# testerusb.net
KiCad netlist of a schematic drawn in EAGLE
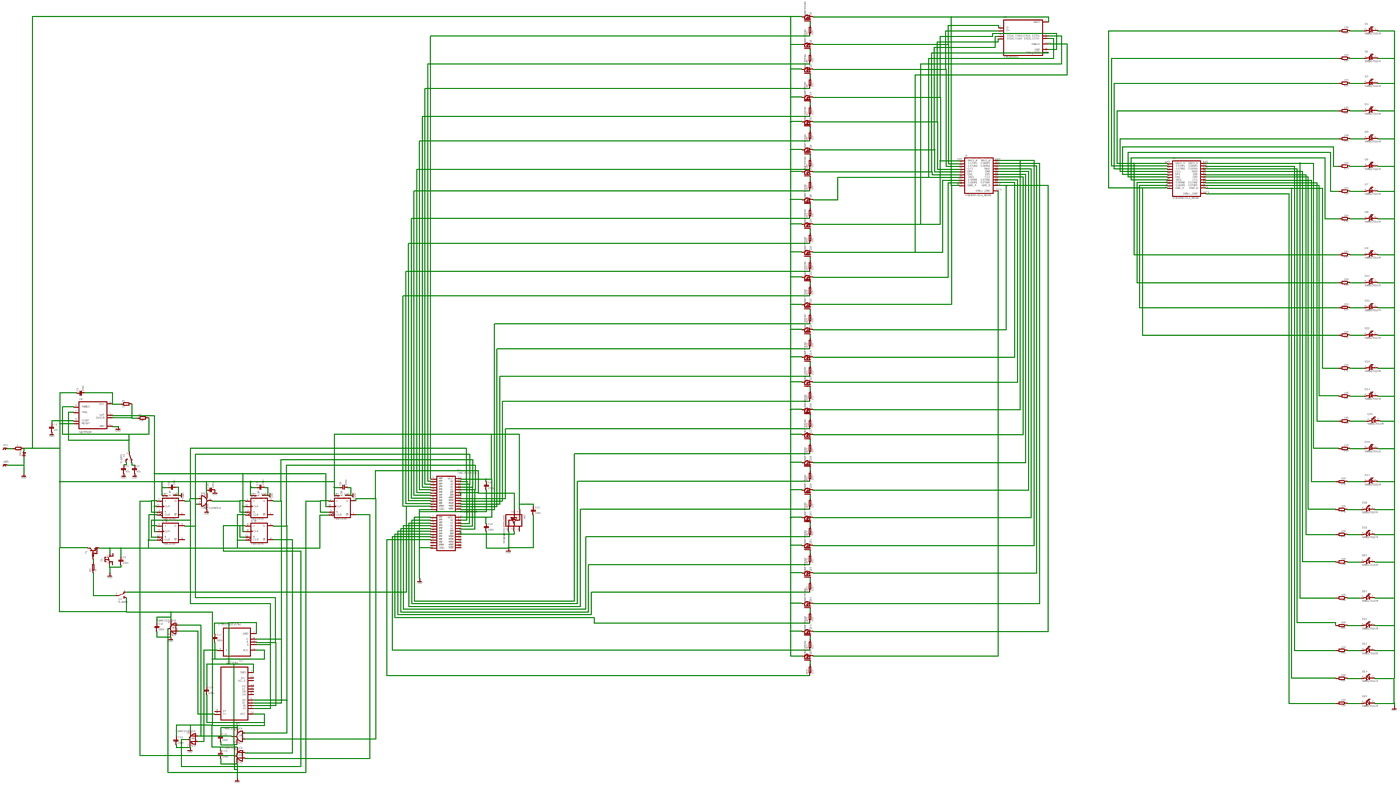
[diagram p0: schematic, sheet 1, overview]
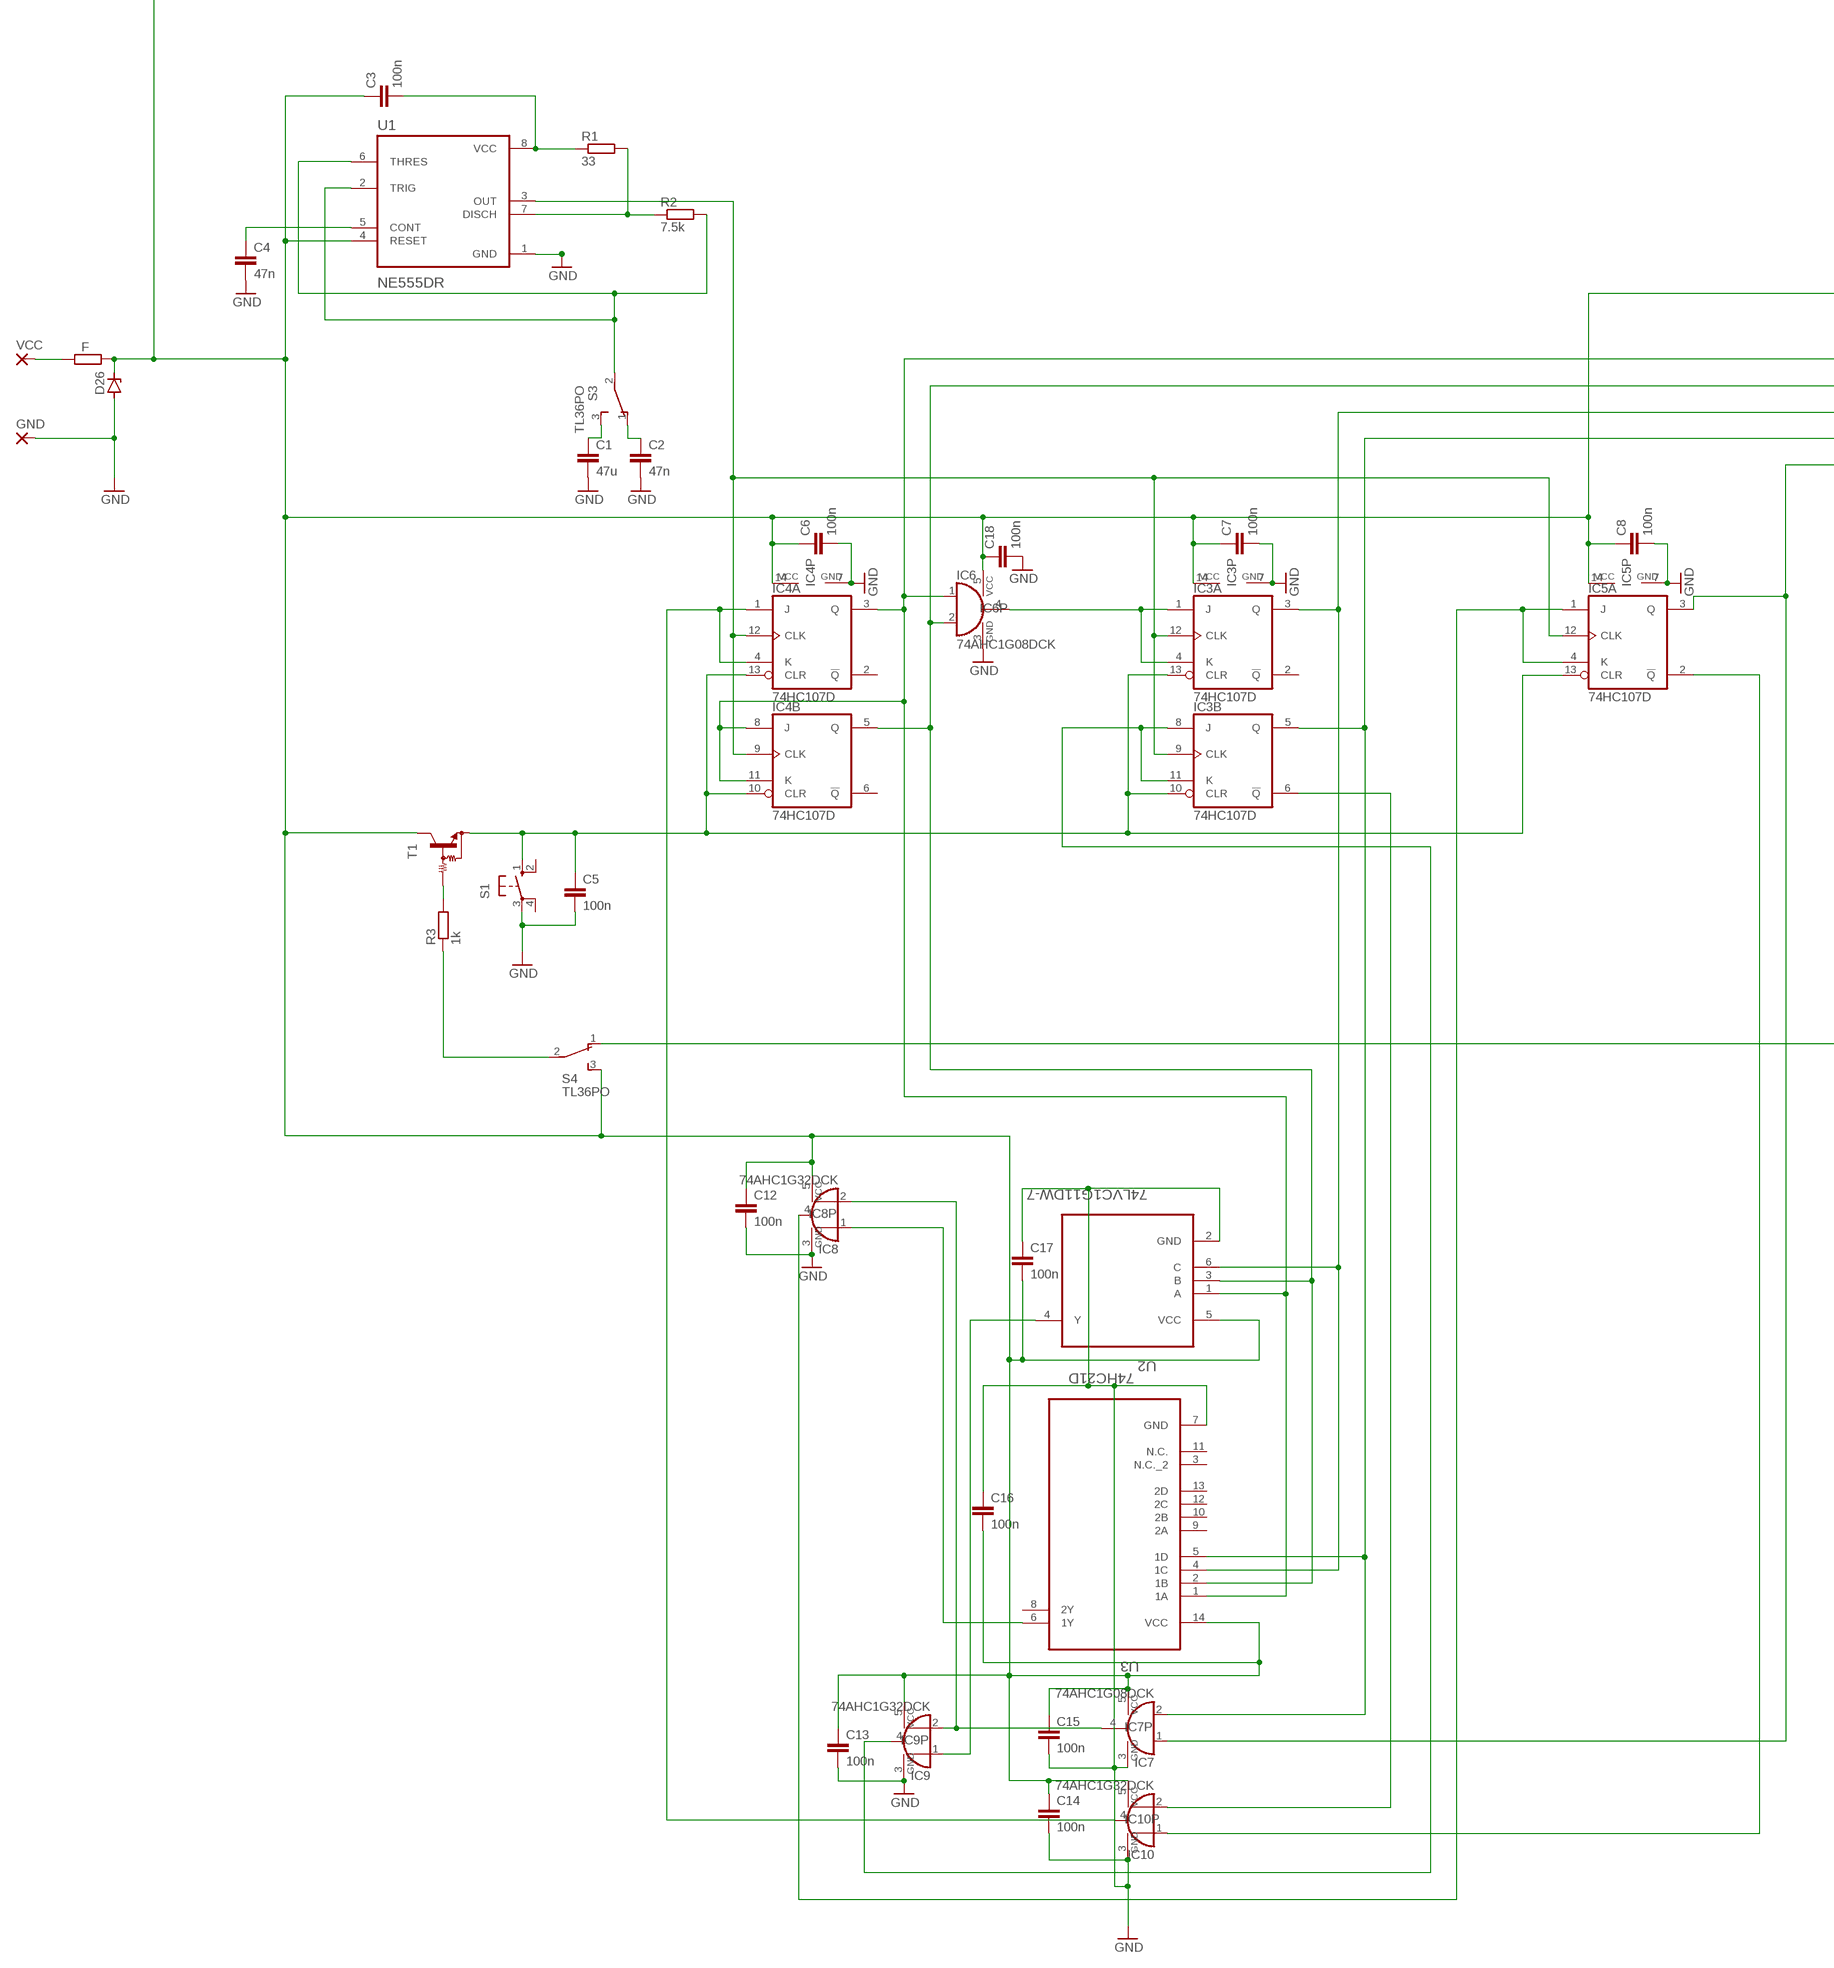
[diagram p1: schematic, sheet 1, part 1 of 6]
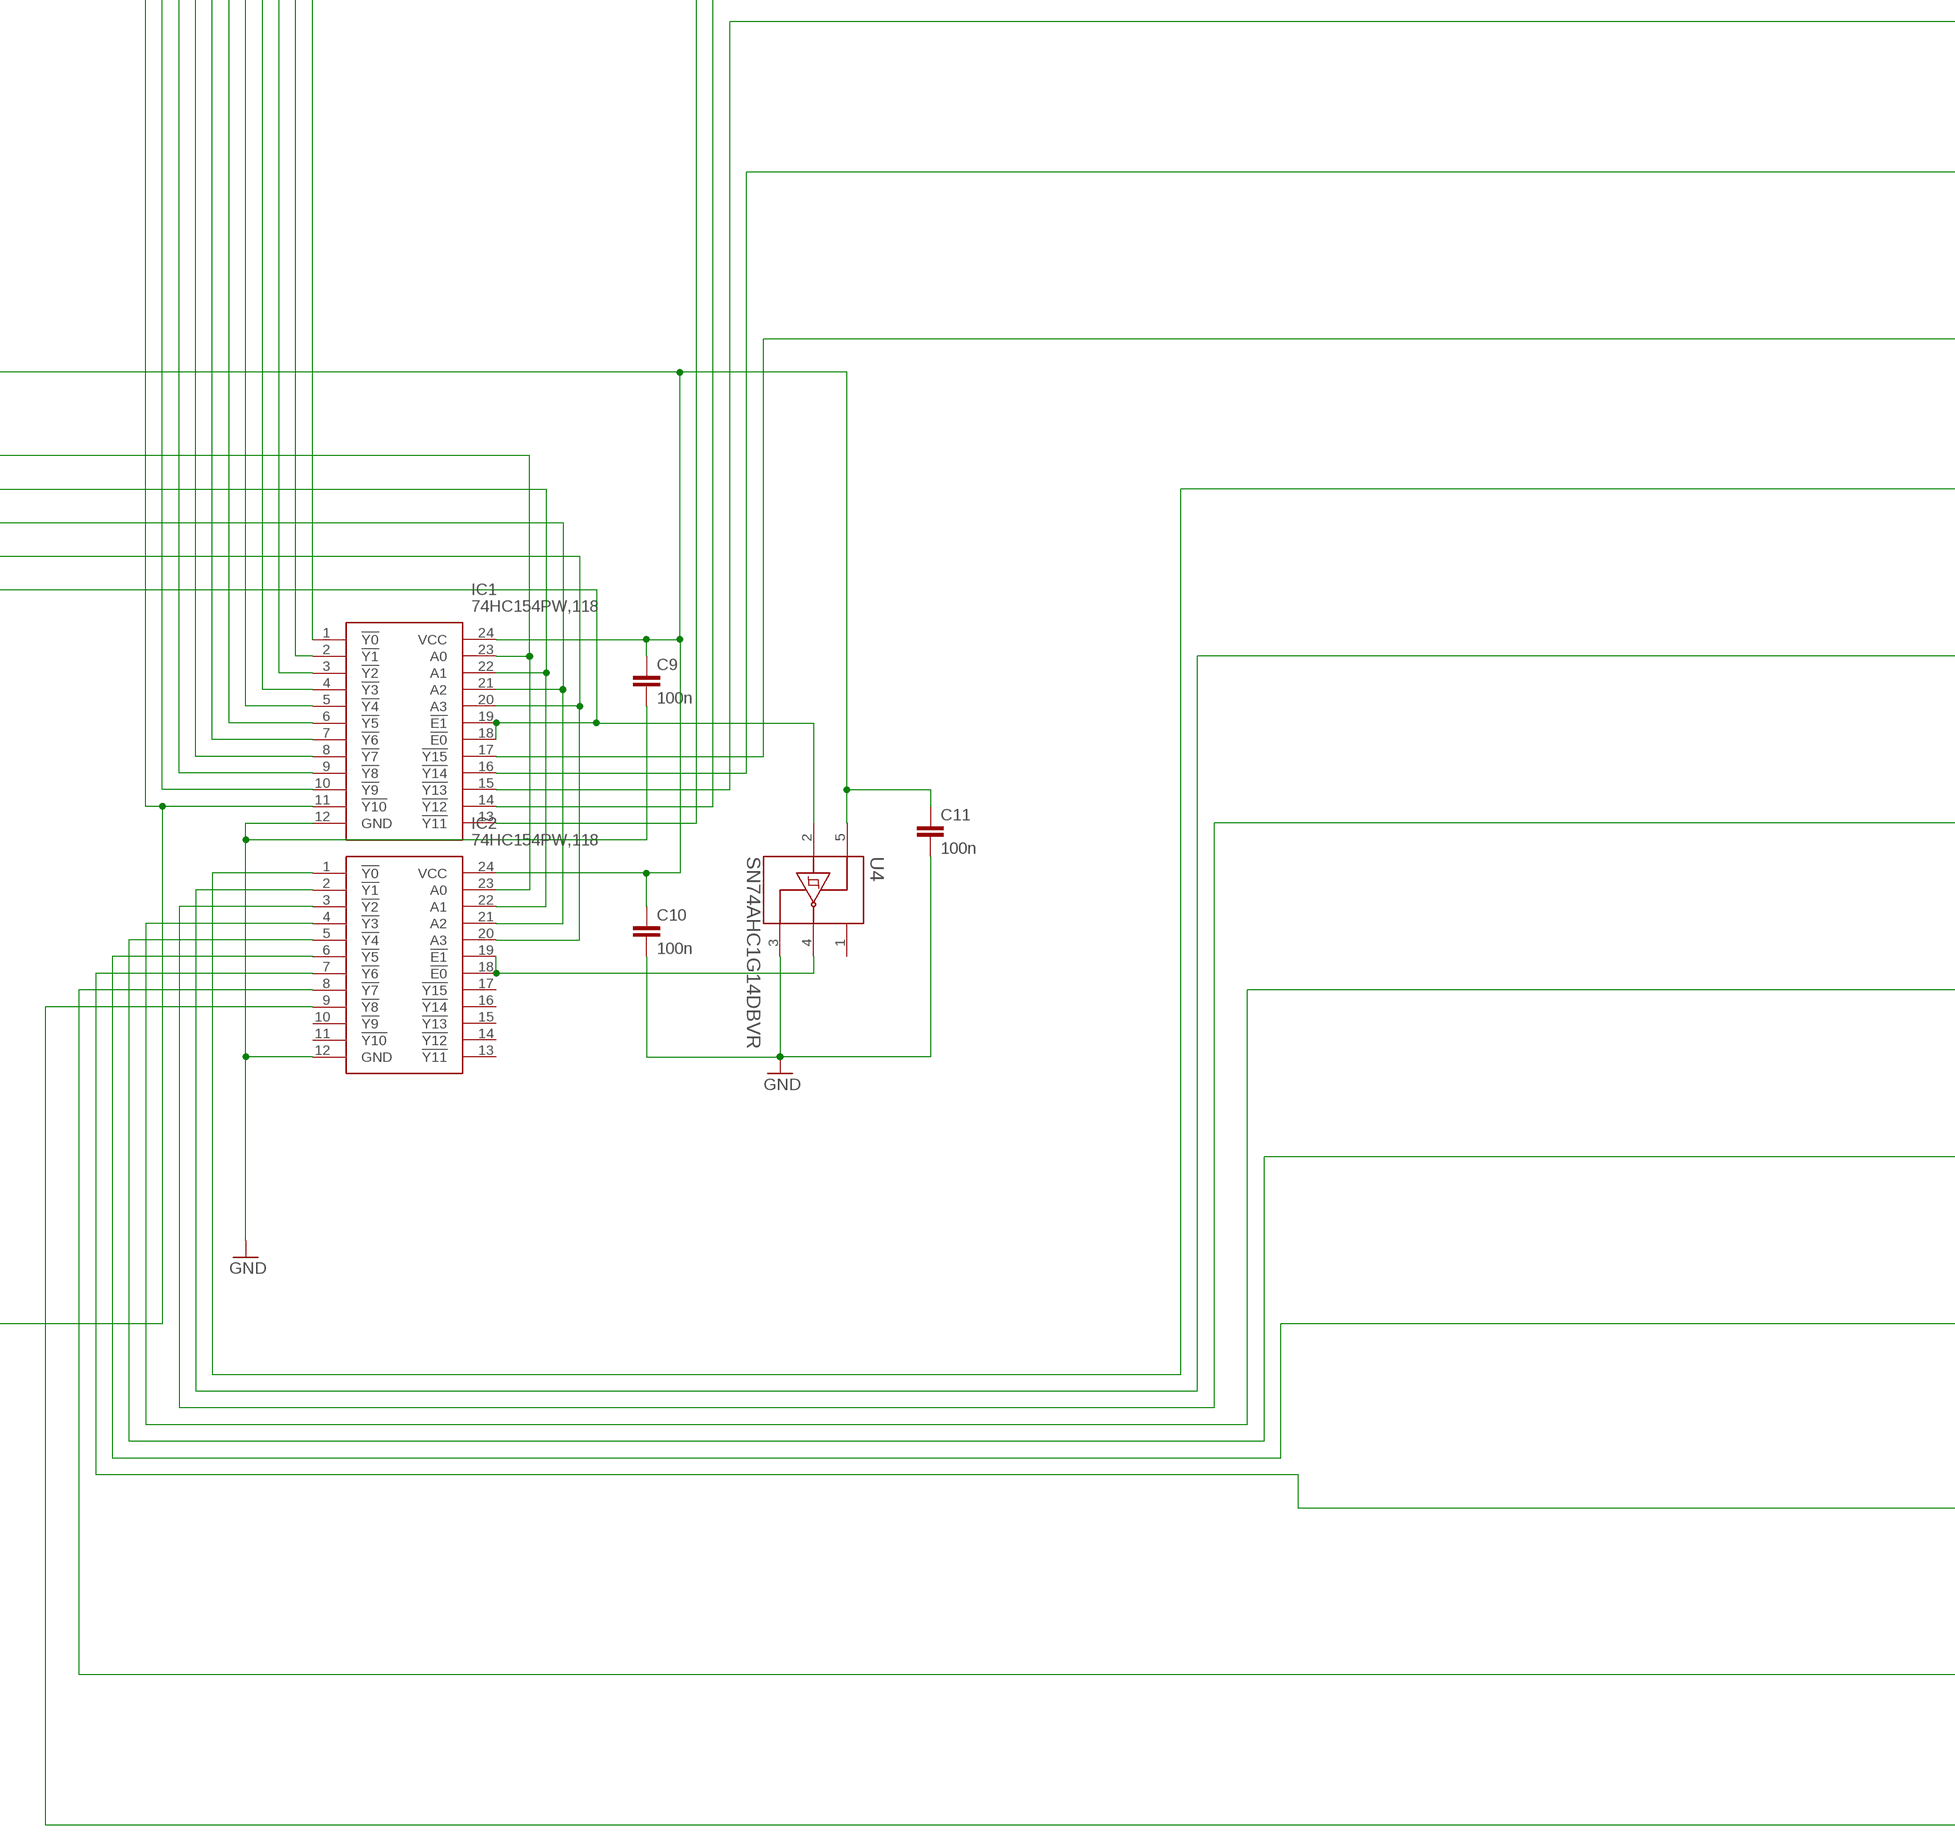
[diagram p2: schematic, sheet 1, part 2 of 6]
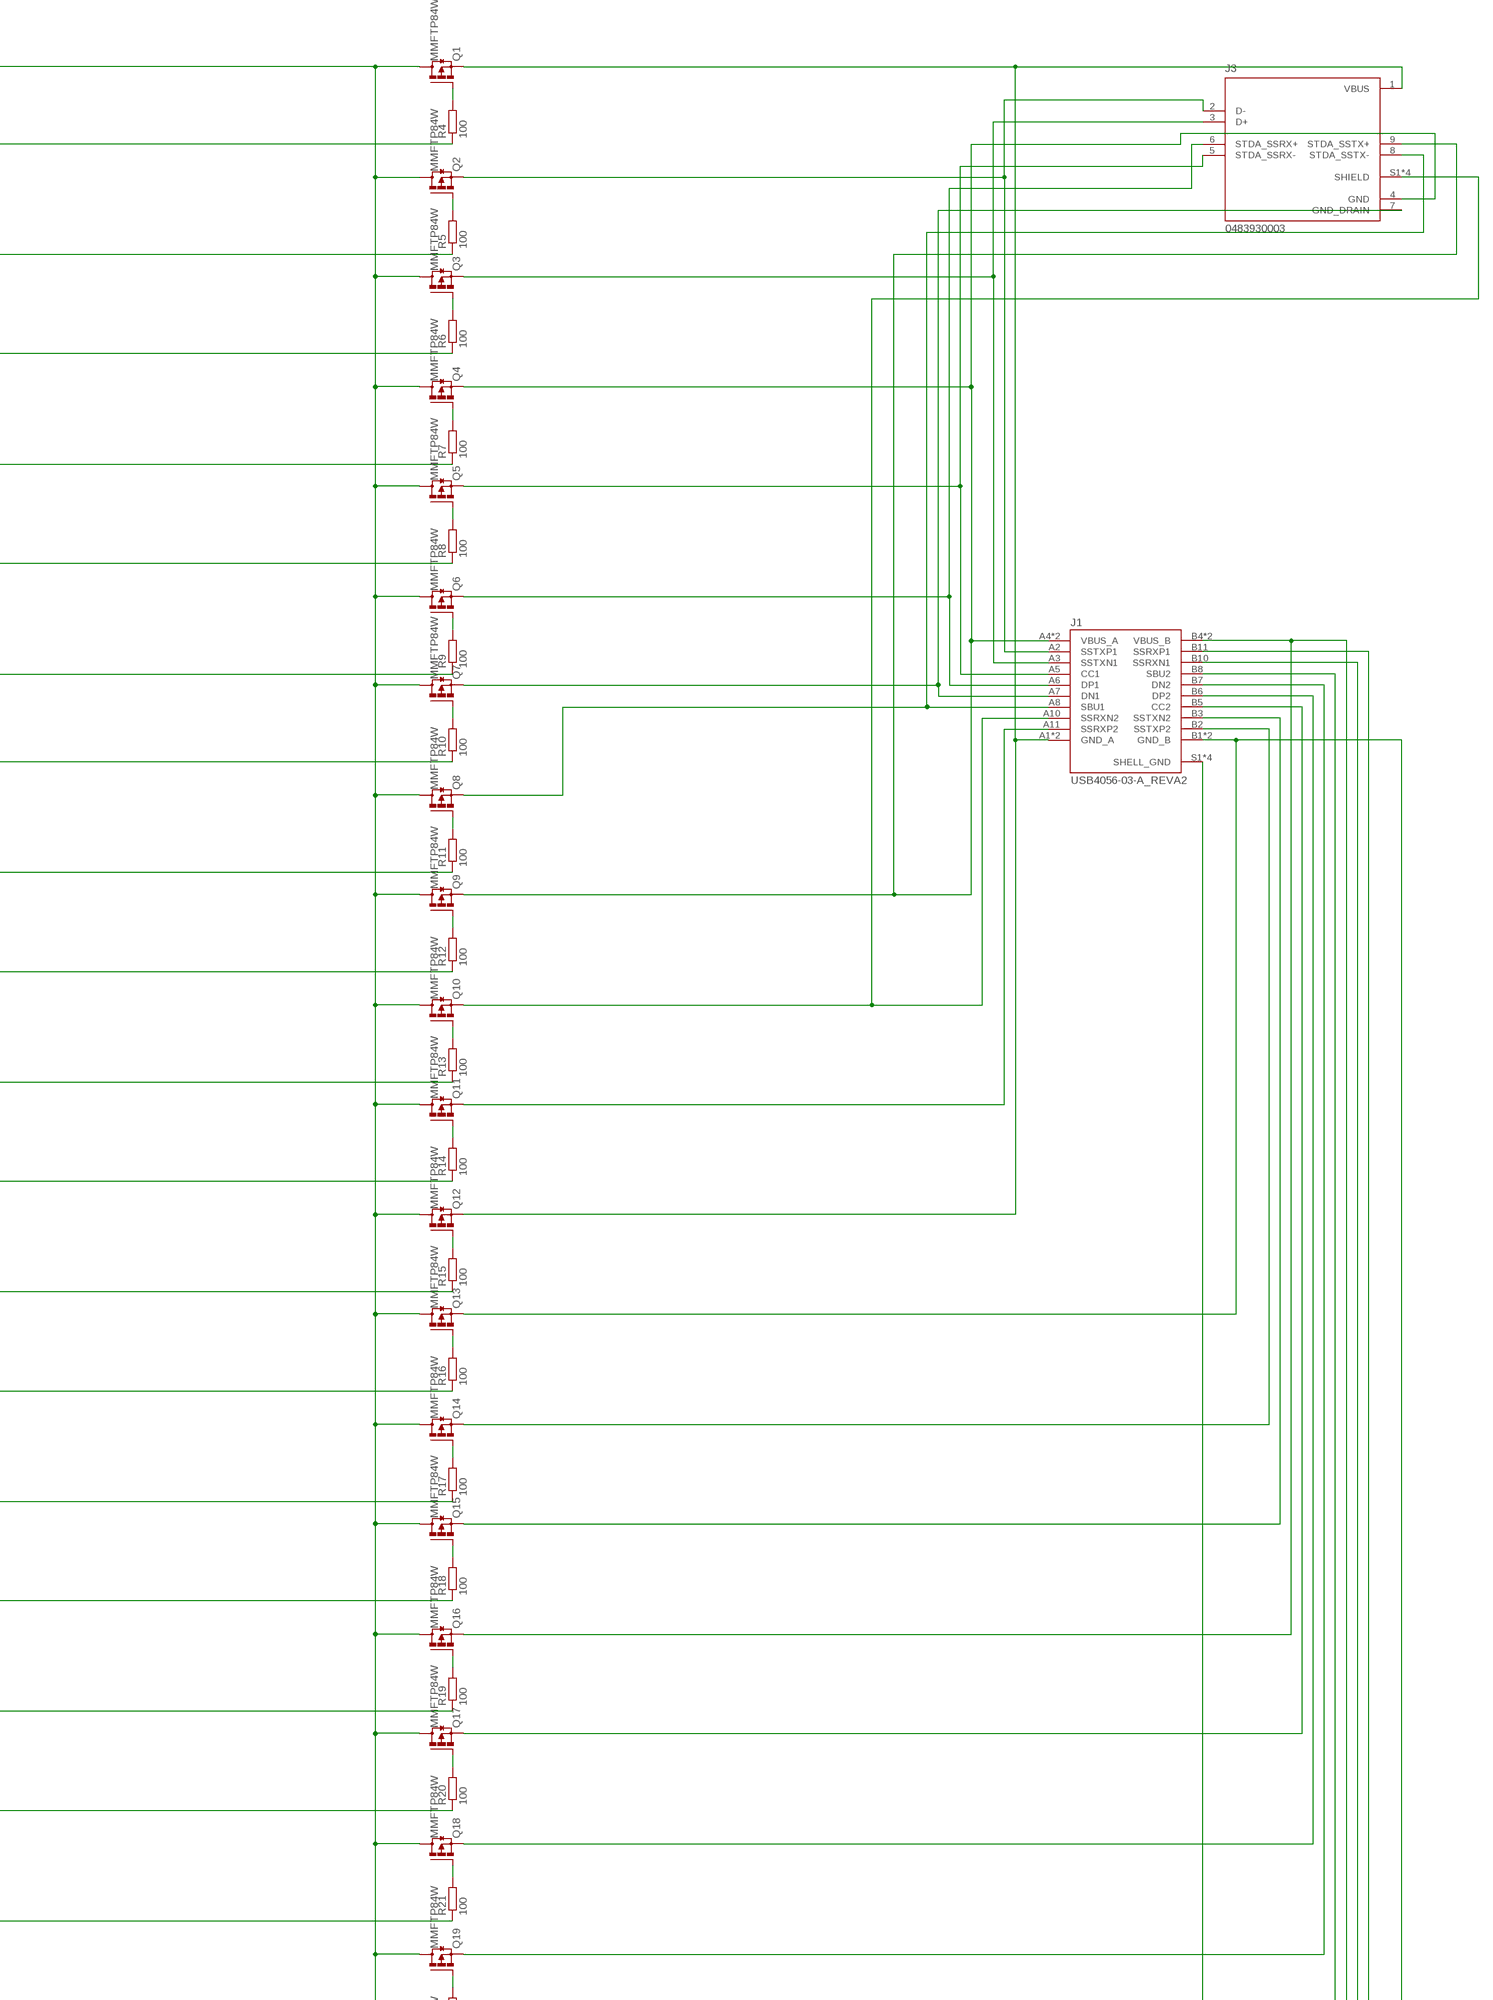
[diagram p3: schematic, sheet 1, part 3 of 6]
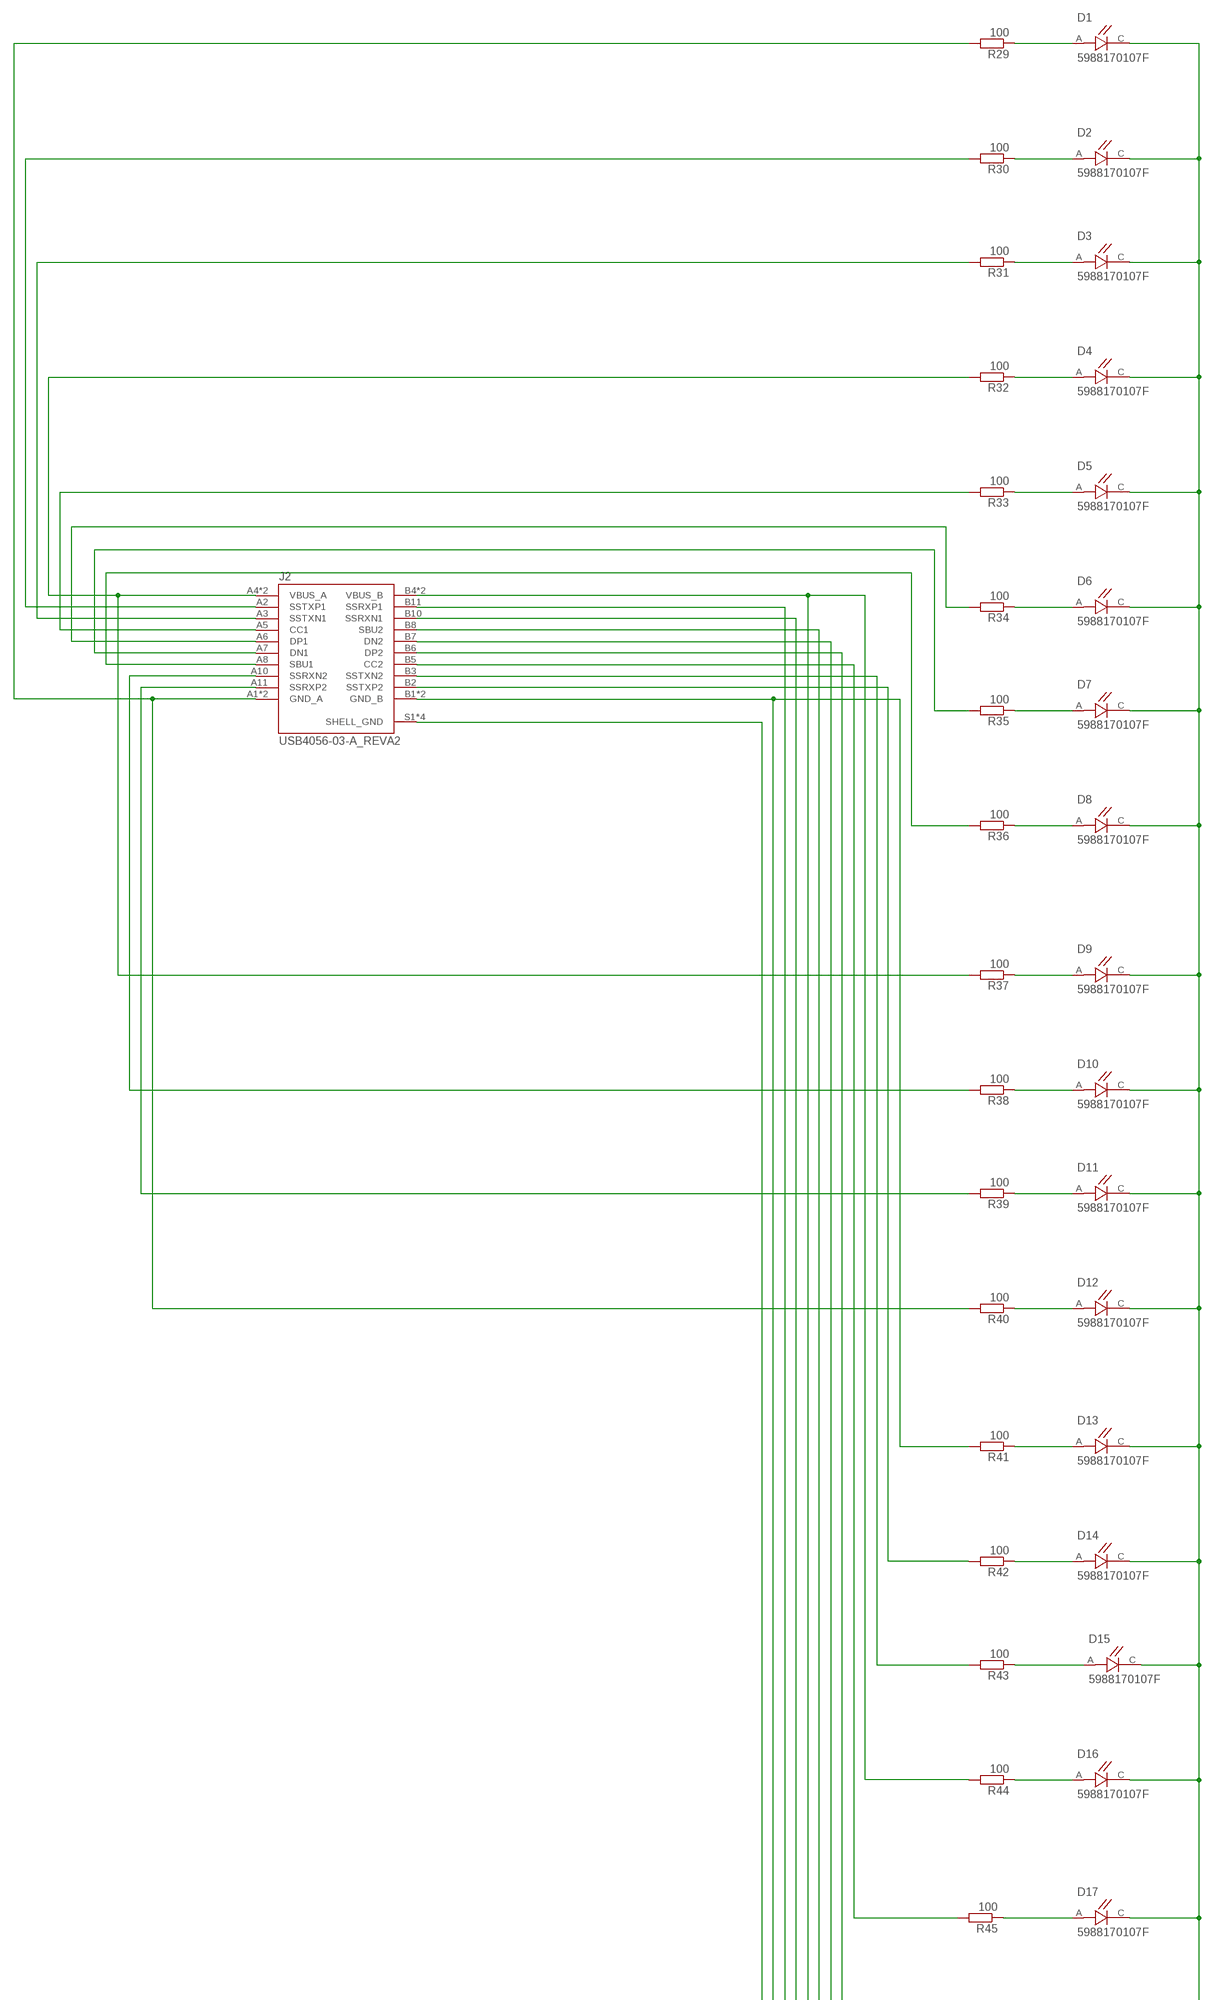
[diagram p4: schematic, sheet 1, part 4 of 6]
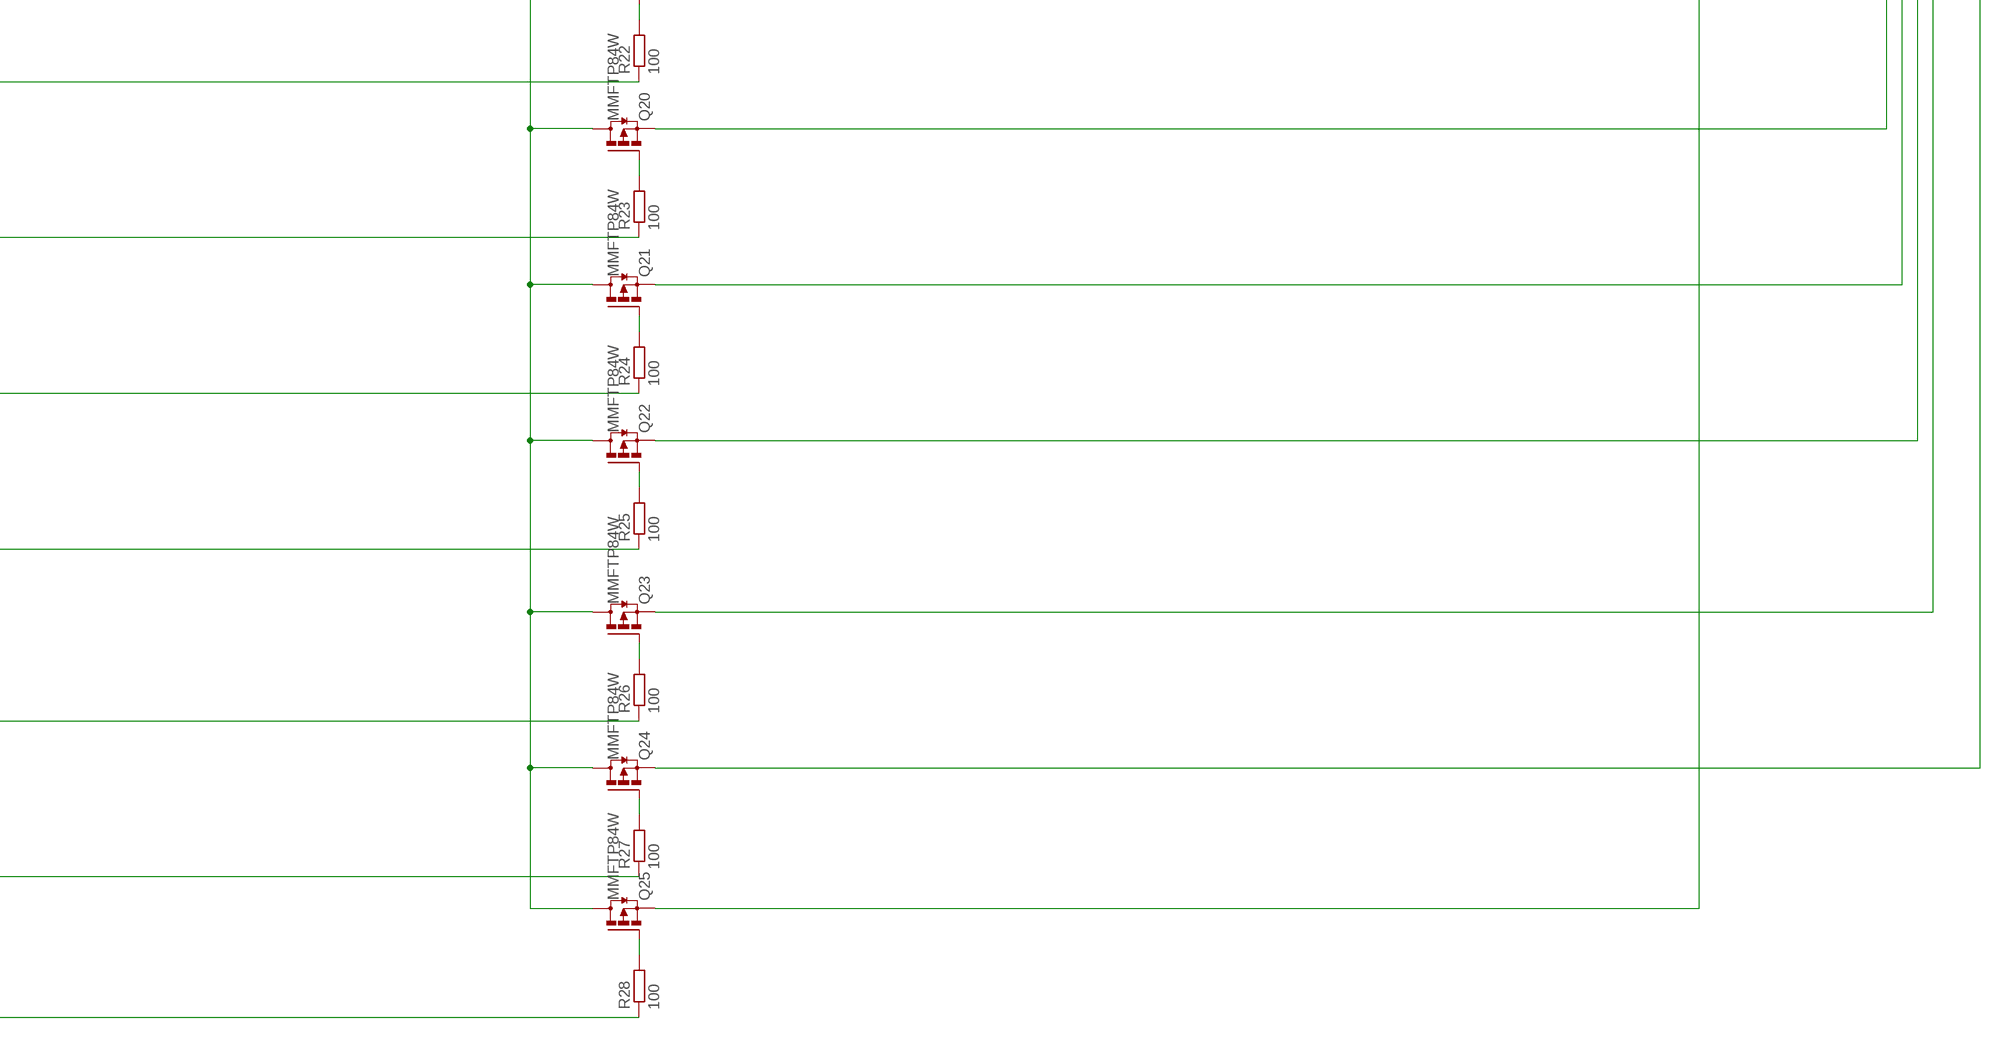
[diagram p5: schematic, sheet 1, part 5 of 6]
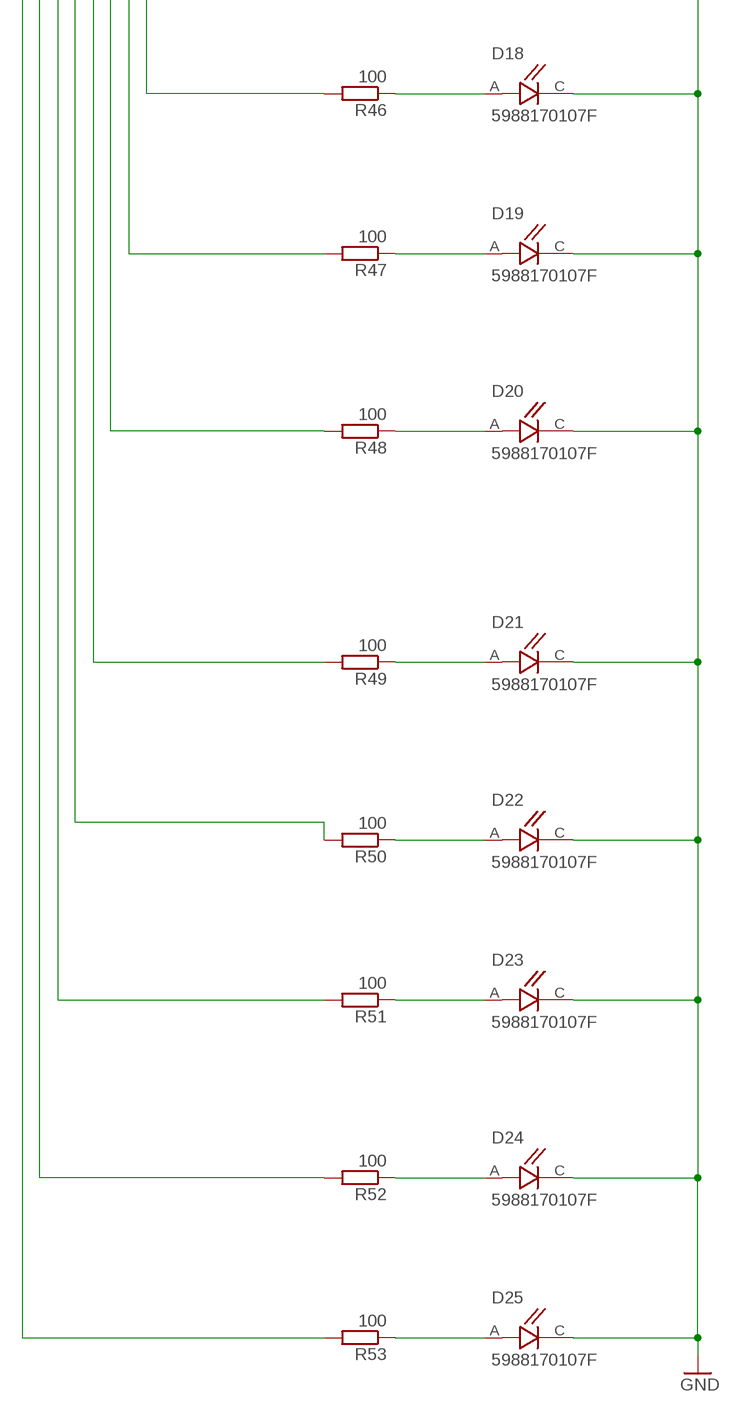
[diagram p6: schematic, sheet 1, part 6 of 6]

(export (version "E")
  (design (tool "Eeschema 10.0.6"))
  (components
    (comp (ref "C1")
      (value "47u")
      (footprint "eagle-import:C025_050-035X075")
      (libsource (lib "eagle-import") (part "C-EU025_050-035X075"))
    )
    (comp (ref "C2")
      (value "47n")
      (footprint "eagle-import:C025_050-035X075")
      (libsource (lib "eagle-import") (part "C-EU025_050-035X075"))
    )
    (comp (ref "C3")
      (value "100n")
      (footprint "eagle-import:C0805")
      (libsource (lib "eagle-import") (part "C-EUC0805"))
    )
    (comp (ref "C4")
      (value "47n")
      (footprint "eagle-import:C025_050-035X075")
      (libsource (lib "eagle-import") (part "C-EU025_050-035X075"))
    )
    (comp (ref "C5")
      (value "100n")
      (footprint "eagle-import:C0805")
      (libsource (lib "eagle-import") (part "C-EUC0805"))
    )
    (comp (ref "C6")
      (value "100n")
      (footprint "eagle-import:C0805")
      (libsource (lib "eagle-import") (part "C-EUC0805"))
    )
    (comp (ref "C7")
      (value "100n")
      (footprint "eagle-import:C0805")
      (libsource (lib "eagle-import") (part "C-EUC0805"))
    )
    (comp (ref "C8")
      (value "100n")
      (footprint "eagle-import:C0805")
      (libsource (lib "eagle-import") (part "C-EUC0805"))
    )
    (comp (ref "C9")
      (value "100n")
      (footprint "eagle-import:C0805")
      (libsource (lib "eagle-import") (part "C-EUC0805"))
    )
    (comp (ref "C10")
      (value "100n")
      (footprint "eagle-import:C0805")
      (libsource (lib "eagle-import") (part "C-EUC0805"))
    )
    (comp (ref "C11")
      (value "100n")
      (footprint "eagle-import:C0805")
      (libsource (lib "eagle-import") (part "C-EUC0805"))
    )
    (comp (ref "C12")
      (value "100n")
      (footprint "eagle-import:C0805")
      (libsource (lib "eagle-import") (part "C-EUC0805"))
    )
    (comp (ref "C13")
      (value "100n")
      (footprint "eagle-import:C0805")
      (libsource (lib "eagle-import") (part "C-EUC0805"))
    )
    (comp (ref "C14")
      (value "100n")
      (footprint "eagle-import:C0805")
      (libsource (lib "eagle-import") (part "C-EUC0805"))
    )
    (comp (ref "C15")
      (value "100n")
      (footprint "eagle-import:C0805")
      (libsource (lib "eagle-import") (part "C-EUC0805"))
    )
    (comp (ref "C16")
      (value "100n")
      (footprint "eagle-import:C0805")
      (libsource (lib "eagle-import") (part "C-EUC0805"))
    )
    (comp (ref "C17")
      (value "100n")
      (footprint "eagle-import:C0805")
      (libsource (lib "eagle-import") (part "C-EUC0805"))
    )
    (comp (ref "C18")
      (value "100n")
      (footprint "eagle-import:C0805")
      (libsource (lib "eagle-import") (part "C-EUC0805"))
    )
    (comp (ref "D1")
      (value "5988170107F")
      (footprint "eagle-import:LEDC2012X70N")
      (fields (field (name "MF") "Dialight"))
      (libsource (lib "eagle-import") (part "5988170107F"))
    )
    (comp (ref "D2")
      (value "5988170107F")
      (footprint "eagle-import:LEDC2012X70N")
      (fields (field (name "MF") "Dialight"))
      (libsource (lib "eagle-import") (part "5988170107F"))
    )
    (comp (ref "D3")
      (value "5988170107F")
      (footprint "eagle-import:LEDC2012X70N")
      (fields (field (name "MF") "Dialight"))
      (libsource (lib "eagle-import") (part "5988170107F"))
    )
    (comp (ref "D4")
      (value "5988170107F")
      (footprint "eagle-import:LEDC2012X70N")
      (fields (field (name "MF") "Dialight"))
      (libsource (lib "eagle-import") (part "5988170107F"))
    )
    (comp (ref "D5")
      (value "5988170107F")
      (footprint "eagle-import:LEDC2012X70N")
      (fields (field (name "MF") "Dialight"))
      (libsource (lib "eagle-import") (part "5988170107F"))
    )
    (comp (ref "D6")
      (value "5988170107F")
      (footprint "eagle-import:LEDC2012X70N")
      (fields (field (name "MF") "Dialight"))
      (libsource (lib "eagle-import") (part "5988170107F"))
    )
    (comp (ref "D7")
      (value "5988170107F")
      (footprint "eagle-import:LEDC2012X70N")
      (fields (field (name "MF") "Dialight"))
      (libsource (lib "eagle-import") (part "5988170107F"))
    )
    (comp (ref "D8")
      (value "5988170107F")
      (footprint "eagle-import:LEDC2012X70N")
      (fields (field (name "MF") "Dialight"))
      (libsource (lib "eagle-import") (part "5988170107F"))
    )
    (comp (ref "D9")
      (value "5988170107F")
      (footprint "eagle-import:LEDC2012X70N")
      (fields (field (name "MF") "Dialight"))
      (libsource (lib "eagle-import") (part "5988170107F"))
    )
    (comp (ref "D10")
      (value "5988170107F")
      (footprint "eagle-import:LEDC2012X70N")
      (fields (field (name "MF") "Dialight"))
      (libsource (lib "eagle-import") (part "5988170107F"))
    )
    (comp (ref "D11")
      (value "5988170107F")
      (footprint "eagle-import:LEDC2012X70N")
      (fields (field (name "MF") "Dialight"))
      (libsource (lib "eagle-import") (part "5988170107F"))
    )
    (comp (ref "D12")
      (value "5988170107F")
      (footprint "eagle-import:LEDC2012X70N")
      (fields (field (name "MF") "Dialight"))
      (libsource (lib "eagle-import") (part "5988170107F"))
    )
    (comp (ref "D13")
      (value "5988170107F")
      (footprint "eagle-import:LEDC2012X70N")
      (fields (field (name "MF") "Dialight"))
      (libsource (lib "eagle-import") (part "5988170107F"))
    )
    (comp (ref "D14")
      (value "5988170107F")
      (footprint "eagle-import:LEDC2012X70N")
      (fields (field (name "MF") "Dialight"))
      (libsource (lib "eagle-import") (part "5988170107F"))
    )
    (comp (ref "D15")
      (value "5988170107F")
      (footprint "eagle-import:LEDC2012X70N")
      (fields (field (name "MF") "Dialight"))
      (libsource (lib "eagle-import") (part "5988170107F"))
    )
    (comp (ref "D16")
      (value "5988170107F")
      (footprint "eagle-import:LEDC2012X70N")
      (fields (field (name "MF") "Dialight"))
      (libsource (lib "eagle-import") (part "5988170107F"))
    )
    (comp (ref "D17")
      (value "5988170107F")
      (footprint "eagle-import:LEDC2012X70N")
      (fields (field (name "MF") "Dialight"))
      (libsource (lib "eagle-import") (part "5988170107F"))
    )
    (comp (ref "D18")
      (value "5988170107F")
      (footprint "eagle-import:LEDC2012X70N")
      (fields (field (name "MF") "Dialight"))
      (libsource (lib "eagle-import") (part "5988170107F"))
    )
    (comp (ref "D19")
      (value "5988170107F")
      (footprint "eagle-import:LEDC2012X70N")
      (fields (field (name "MF") "Dialight"))
      (libsource (lib "eagle-import") (part "5988170107F"))
    )
    (comp (ref "D20")
      (value "5988170107F")
      (footprint "eagle-import:LEDC2012X70N")
      (fields (field (name "MF") "Dialight"))
      (libsource (lib "eagle-import") (part "5988170107F"))
    )
    (comp (ref "D21")
      (value "5988170107F")
      (footprint "eagle-import:LEDC2012X70N")
      (fields (field (name "MF") "Dialight"))
      (libsource (lib "eagle-import") (part "5988170107F"))
    )
    (comp (ref "D22")
      (value "5988170107F")
      (footprint "eagle-import:LEDC2012X70N")
      (fields (field (name "MF") "Dialight"))
      (libsource (lib "eagle-import") (part "5988170107F"))
    )
    (comp (ref "D23")
      (value "5988170107F")
      (footprint "eagle-import:LEDC2012X70N")
      (fields (field (name "MF") "Dialight"))
      (libsource (lib "eagle-import") (part "5988170107F"))
    )
    (comp (ref "D24")
      (value "5988170107F")
      (footprint "eagle-import:LEDC2012X70N")
      (fields (field (name "MF") "Dialight"))
      (libsource (lib "eagle-import") (part "5988170107F"))
    )
    (comp (ref "D25")
      (value "5988170107F")
      (footprint "eagle-import:LEDC2012X70N")
      (fields (field (name "MF") "Dialight"))
      (libsource (lib "eagle-import") (part "5988170107F"))
    )
    (comp (ref "D26")
      (value "ZENER-DIODEP1-12")
      (footprint "eagle-import:P1Z12")
      (libsource (lib "eagle-import") (part "ZENER-DIODEP1-12"))
    )
    (comp (ref "F")
      (value "R-EU_1812X7R")
      (footprint "eagle-import:1812X7R")
      (libsource (lib "eagle-import") (part "R-EU_1812X7R"))
    )
    (comp (ref "GND")
      (value "3,81/1,4")
      (footprint "eagle-import:3,81_1,4")
      (libsource (lib "eagle-import") (part "3,81/1,4"))
    )
    (comp (ref "IC1")
      (value "74HC154PW,118")
      (footprint "eagle-import:SOP65P640X110-24N")
      (fields (field (name "MOUSER_PART_NUMBER") "771-HC154PW118"))
      (libsource (lib "eagle-import") (part "74HC154PW,118"))
    )
    (comp (ref "IC2")
      (value "74HC154PW,118")
      (footprint "eagle-import:SOP65P640X110-24N")
      (fields (field (name "MOUSER_PART_NUMBER") "771-HC154PW118"))
      (libsource (lib "eagle-import") (part "74HC154PW,118"))
    )
    (comp (ref "IC3")
      (value "74HC107D")
      (footprint "eagle-import:SO14")
      (libsource (lib "eagle-import") (part "74107DHC"))
    )
    (comp (ref "IC4")
      (value "74HC107D")
      (footprint "eagle-import:SO14")
      (libsource (lib "eagle-import") (part "74107DHC"))
    )
    (comp (ref "IC5")
      (value "74HC107D")
      (footprint "eagle-import:SO14")
      (libsource (lib "eagle-import") (part "74107DHC"))
    )
    (comp (ref "IC6")
      (value "74AHC1G08DCK")
      (footprint "eagle-import:SC70-5")
      (libsource (lib "eagle-import") (part "741G08DCKAHC"))
    )
    (comp (ref "IC7")
      (value "74AHC1G08DCK")
      (footprint "eagle-import:SC70-5")
      (libsource (lib "eagle-import") (part "741G08DCKAHC"))
    )
    (comp (ref "IC8")
      (value "74AHC1G32DCK")
      (footprint "eagle-import:SC70-5")
      (libsource (lib "eagle-import") (part "741G32DCKAHC"))
    )
    (comp (ref "IC9")
      (value "74AHC1G32DCK")
      (footprint "eagle-import:SC70-5")
      (libsource (lib "eagle-import") (part "741G32DCKAHC"))
    )
    (comp (ref "IC10")
      (value "74AHC1G32DCK")
      (footprint "eagle-import:SC70-5")
      (libsource (lib "eagle-import") (part "741G32DCKAHC"))
    )
    (comp (ref "J1")
      (value "USB4056-03-A_REVA2")
      (footprint "eagle-import:GCT_USB4056-03-A_REVA2")
      (fields (field (name "MF") "Global Connector Technology") (field (name "MP") "USB4056-03-A"))
      (libsource (lib "eagle-import") (part "USB4056-03-A_REVA2"))
    )
    (comp (ref "J2")
      (value "USB4056-03-A_REVA2")
      (footprint "eagle-import:GCT_USB4056-03-A_REVA2")
      (fields (field (name "MF") "Global Connector Technology") (field (name "MP") "USB4056-03-A"))
      (libsource (lib "eagle-import") (part "USB4056-03-A_REVA2"))
    )
    (comp (ref "J3")
      (value "0483930003")
      (footprint "eagle-import:MOLEX_0483930003")
      (fields (field (name "MF") "Molex"))
      (libsource (lib "eagle-import") (part "0483930003"))
    )
    (comp (ref "Q1")
      (value "MMFTP84W")
      (footprint "eagle-import:SUPER-SOT3")
      (libsource (lib "eagle-import") (part "FDN360P"))
    )
    (comp (ref "Q2")
      (value "MMFTP84W")
      (footprint "eagle-import:SUPER-SOT3")
      (libsource (lib "eagle-import") (part "FDN360P"))
    )
    (comp (ref "Q3")
      (value "MMFTP84W")
      (footprint "eagle-import:SUPER-SOT3")
      (libsource (lib "eagle-import") (part "FDN360P"))
    )
    (comp (ref "Q4")
      (value "MMFTP84W")
      (footprint "eagle-import:SUPER-SOT3")
      (libsource (lib "eagle-import") (part "FDN360P"))
    )
    (comp (ref "Q5")
      (value "MMFTP84W")
      (footprint "eagle-import:SUPER-SOT3")
      (libsource (lib "eagle-import") (part "FDN360P"))
    )
    (comp (ref "Q6")
      (value "MMFTP84W")
      (footprint "eagle-import:SUPER-SOT3")
      (libsource (lib "eagle-import") (part "FDN360P"))
    )
    (comp (ref "Q7")
      (value "MMFTP84W")
      (footprint "eagle-import:SUPER-SOT3")
      (libsource (lib "eagle-import") (part "FDN360P"))
    )
    (comp (ref "Q8")
      (value "MMFTP84W")
      (footprint "eagle-import:SUPER-SOT3")
      (libsource (lib "eagle-import") (part "FDN360P"))
    )
    (comp (ref "Q9")
      (value "MMFTP84W")
      (footprint "eagle-import:SUPER-SOT3")
      (libsource (lib "eagle-import") (part "FDN360P"))
    )
    (comp (ref "Q10")
      (value "MMFTP84W")
      (footprint "eagle-import:SUPER-SOT3")
      (libsource (lib "eagle-import") (part "FDN360P"))
    )
    (comp (ref "Q11")
      (value "MMFTP84W")
      (footprint "eagle-import:SUPER-SOT3")
      (libsource (lib "eagle-import") (part "FDN360P"))
    )
    (comp (ref "Q12")
      (value "MMFTP84W")
      (footprint "eagle-import:SUPER-SOT3")
      (libsource (lib "eagle-import") (part "FDN360P"))
    )
    (comp (ref "Q13")
      (value "MMFTP84W")
      (footprint "eagle-import:SUPER-SOT3")
      (libsource (lib "eagle-import") (part "FDN360P"))
    )
    (comp (ref "Q14")
      (value "MMFTP84W")
      (footprint "eagle-import:SUPER-SOT3")
      (libsource (lib "eagle-import") (part "FDN360P"))
    )
    (comp (ref "Q15")
      (value "MMFTP84W")
      (footprint "eagle-import:SUPER-SOT3")
      (libsource (lib "eagle-import") (part "FDN360P"))
    )
    (comp (ref "Q16")
      (value "MMFTP84W")
      (footprint "eagle-import:SUPER-SOT3")
      (libsource (lib "eagle-import") (part "FDN360P"))
    )
    (comp (ref "Q17")
      (value "MMFTP84W")
      (footprint "eagle-import:SUPER-SOT3")
      (libsource (lib "eagle-import") (part "FDN360P"))
    )
    (comp (ref "Q18")
      (value "MMFTP84W")
      (footprint "eagle-import:SUPER-SOT3")
      (libsource (lib "eagle-import") (part "FDN360P"))
    )
    (comp (ref "Q19")
      (value "MMFTP84W")
      (footprint "eagle-import:SUPER-SOT3")
      (libsource (lib "eagle-import") (part "FDN360P"))
    )
    (comp (ref "Q20")
      (value "MMFTP84W")
      (footprint "eagle-import:SUPER-SOT3")
      (libsource (lib "eagle-import") (part "FDN360P"))
    )
    (comp (ref "Q21")
      (value "MMFTP84W")
      (footprint "eagle-import:SUPER-SOT3")
      (libsource (lib "eagle-import") (part "FDN360P"))
    )
    (comp (ref "Q22")
      (value "MMFTP84W")
      (footprint "eagle-import:SUPER-SOT3")
      (libsource (lib "eagle-import") (part "FDN360P"))
    )
    (comp (ref "Q23")
      (value "MMFTP84W")
      (footprint "eagle-import:SUPER-SOT3")
      (libsource (lib "eagle-import") (part "FDN360P"))
    )
    (comp (ref "Q24")
      (value "MMFTP84W")
      (footprint "eagle-import:SUPER-SOT3")
      (libsource (lib "eagle-import") (part "FDN360P"))
    )
    (comp (ref "Q25")
      (value "MMFTP84W")
      (footprint "eagle-import:SUPER-SOT3")
      (libsource (lib "eagle-import") (part "FDN360P"))
    )
    (comp (ref "R1")
      (value "33")
      (footprint "eagle-import:0207_10")
      (libsource (lib "eagle-import") (part "R-EU_0207/10"))
    )
    (comp (ref "R2")
      (value "7.5k")
      (footprint "eagle-import:0207_10")
      (libsource (lib "eagle-import") (part "R-EU_0207/10"))
    )
    (comp (ref "R3")
      (value "1k")
      (footprint "eagle-import:R0805")
      (libsource (lib "eagle-import") (part "R-EU_R0805"))
    )
    (comp (ref "R4")
      (value "100")
      (footprint "eagle-import:R0805")
      (libsource (lib "eagle-import") (part "R-EU_R0805"))
    )
    (comp (ref "R5")
      (value "100")
      (footprint "eagle-import:R0805")
      (libsource (lib "eagle-import") (part "R-EU_R0805"))
    )
    (comp (ref "R6")
      (value "100")
      (footprint "eagle-import:R0805")
      (libsource (lib "eagle-import") (part "R-EU_R0805"))
    )
    (comp (ref "R7")
      (value "100")
      (footprint "eagle-import:R0805")
      (libsource (lib "eagle-import") (part "R-EU_R0805"))
    )
    (comp (ref "R8")
      (value "100")
      (footprint "eagle-import:R0805")
      (libsource (lib "eagle-import") (part "R-EU_R0805"))
    )
    (comp (ref "R9")
      (value "100")
      (footprint "eagle-import:R0805")
      (libsource (lib "eagle-import") (part "R-EU_R0805"))
    )
    (comp (ref "R10")
      (value "100")
      (footprint "eagle-import:R0805")
      (libsource (lib "eagle-import") (part "R-EU_R0805"))
    )
    (comp (ref "R11")
      (value "100")
      (footprint "eagle-import:R0805")
      (libsource (lib "eagle-import") (part "R-EU_R0805"))
    )
    (comp (ref "R12")
      (value "100")
      (footprint "eagle-import:R0805")
      (libsource (lib "eagle-import") (part "R-EU_R0805"))
    )
    (comp (ref "R13")
      (value "100")
      (footprint "eagle-import:R0805")
      (libsource (lib "eagle-import") (part "R-EU_R0805"))
    )
    (comp (ref "R14")
      (value "100")
      (footprint "eagle-import:R0805")
      (libsource (lib "eagle-import") (part "R-EU_R0805"))
    )
    (comp (ref "R15")
      (value "100")
      (footprint "eagle-import:R0805")
      (libsource (lib "eagle-import") (part "R-EU_R0805"))
    )
    (comp (ref "R16")
      (value "100")
      (footprint "eagle-import:R0805")
      (libsource (lib "eagle-import") (part "R-EU_R0805"))
    )
    (comp (ref "R17")
      (value "100")
      (footprint "eagle-import:R0805")
      (libsource (lib "eagle-import") (part "R-EU_R0805"))
    )
    (comp (ref "R18")
      (value "100")
      (footprint "eagle-import:R0805")
      (libsource (lib "eagle-import") (part "R-EU_R0805"))
    )
    (comp (ref "R19")
      (value "100")
      (footprint "eagle-import:R0805")
      (libsource (lib "eagle-import") (part "R-EU_R0805"))
    )
    (comp (ref "R20")
      (value "100")
      (footprint "eagle-import:R0805")
      (libsource (lib "eagle-import") (part "R-EU_R0805"))
    )
    (comp (ref "R21")
      (value "100")
      (footprint "eagle-import:R0805")
      (libsource (lib "eagle-import") (part "R-EU_R0805"))
    )
    (comp (ref "R22")
      (value "100")
      (footprint "eagle-import:R0805")
      (libsource (lib "eagle-import") (part "R-EU_R0805"))
    )
    (comp (ref "R23")
      (value "100")
      (footprint "eagle-import:R0805")
      (libsource (lib "eagle-import") (part "R-EU_R0805"))
    )
    (comp (ref "R24")
      (value "100")
      (footprint "eagle-import:R0805")
      (libsource (lib "eagle-import") (part "R-EU_R0805"))
    )
    (comp (ref "R25")
      (value "100")
      (footprint "eagle-import:R0805")
      (libsource (lib "eagle-import") (part "R-EU_R0805"))
    )
    (comp (ref "R26")
      (value "100")
      (footprint "eagle-import:R0805")
      (libsource (lib "eagle-import") (part "R-EU_R0805"))
    )
    (comp (ref "R27")
      (value "100")
      (footprint "eagle-import:R0805")
      (libsource (lib "eagle-import") (part "R-EU_R0805"))
    )
    (comp (ref "R28")
      (value "100")
      (footprint "eagle-import:R0805")
      (libsource (lib "eagle-import") (part "R-EU_R0805"))
    )
    (comp (ref "R29")
      (value "100")
      (footprint "eagle-import:R0805")
      (libsource (lib "eagle-import") (part "R-EU_R0805"))
    )
    (comp (ref "R30")
      (value "100")
      (footprint "eagle-import:R0805")
      (libsource (lib "eagle-import") (part "R-EU_R0805"))
    )
    (comp (ref "R31")
      (value "100")
      (footprint "eagle-import:R0805")
      (libsource (lib "eagle-import") (part "R-EU_R0805"))
    )
    (comp (ref "R32")
      (value "100")
      (footprint "eagle-import:R0805")
      (libsource (lib "eagle-import") (part "R-EU_R0805"))
    )
    (comp (ref "R33")
      (value "100")
      (footprint "eagle-import:R0805")
      (libsource (lib "eagle-import") (part "R-EU_R0805"))
    )
    (comp (ref "R34")
      (value "100")
      (footprint "eagle-import:R0805")
      (libsource (lib "eagle-import") (part "R-EU_R0805"))
    )
    (comp (ref "R35")
      (value "100")
      (footprint "eagle-import:R0805")
      (libsource (lib "eagle-import") (part "R-EU_R0805"))
    )
    (comp (ref "R36")
      (value "100")
      (footprint "eagle-import:R0805")
      (libsource (lib "eagle-import") (part "R-EU_R0805"))
    )
    (comp (ref "R37")
      (value "100")
      (footprint "eagle-import:R0805")
      (libsource (lib "eagle-import") (part "R-EU_R0805"))
    )
    (comp (ref "R38")
      (value "100")
      (footprint "eagle-import:R0805")
      (libsource (lib "eagle-import") (part "R-EU_R0805"))
    )
    (comp (ref "R39")
      (value "100")
      (footprint "eagle-import:R0805")
      (libsource (lib "eagle-import") (part "R-EU_R0805"))
    )
    (comp (ref "R40")
      (value "100")
      (footprint "eagle-import:R0805")
      (libsource (lib "eagle-import") (part "R-EU_R0805"))
    )
    (comp (ref "R41")
      (value "100")
      (footprint "eagle-import:R0805")
      (libsource (lib "eagle-import") (part "R-EU_R0805"))
    )
    (comp (ref "R42")
      (value "100")
      (footprint "eagle-import:R0805")
      (libsource (lib "eagle-import") (part "R-EU_R0805"))
    )
    (comp (ref "R43")
      (value "100")
      (footprint "eagle-import:R0805")
      (libsource (lib "eagle-import") (part "R-EU_R0805"))
    )
    (comp (ref "R44")
      (value "100")
      (footprint "eagle-import:R0805")
      (libsource (lib "eagle-import") (part "R-EU_R0805"))
    )
    (comp (ref "R45")
      (value "100")
      (footprint "eagle-import:R0805")
      (libsource (lib "eagle-import") (part "R-EU_R0805"))
    )
    (comp (ref "R46")
      (value "100")
      (footprint "eagle-import:R0805")
      (libsource (lib "eagle-import") (part "R-EU_R0805"))
    )
    (comp (ref "R47")
      (value "100")
      (footprint "eagle-import:R0805")
      (libsource (lib "eagle-import") (part "R-EU_R0805"))
    )
    (comp (ref "R48")
      (value "100")
      (footprint "eagle-import:R0805")
      (libsource (lib "eagle-import") (part "R-EU_R0805"))
    )
    (comp (ref "R49")
      (value "100")
      (footprint "eagle-import:R0805")
      (libsource (lib "eagle-import") (part "R-EU_R0805"))
    )
    (comp (ref "R50")
      (value "100")
      (footprint "eagle-import:R0805")
      (libsource (lib "eagle-import") (part "R-EU_R0805"))
    )
    (comp (ref "R51")
      (value "100")
      (footprint "eagle-import:R0805")
      (libsource (lib "eagle-import") (part "R-EU_R0805"))
    )
    (comp (ref "R52")
      (value "100")
      (footprint "eagle-import:R0805")
      (libsource (lib "eagle-import") (part "R-EU_R0805"))
    )
    (comp (ref "R53")
      (value "100")
      (footprint "eagle-import:R0805")
      (libsource (lib "eagle-import") (part "R-EU_R0805"))
    )
    (comp (ref "S1")
      (value "10-XX")
      (footprint "eagle-import:B3F-10XX")
      (fields (field (name "MPN") "B3F-1000"))
      (libsource (lib "eagle-import") (part "10-XX"))
    )
    (comp (ref "S3")
      (value "TL36PO")
      (footprint "eagle-import:TL3XPO")
      (libsource (lib "eagle-import") (part "TL36PO"))
    )
    (comp (ref "S4")
      (value "TL36PO")
      (footprint "eagle-import:TL3XPO")
      (libsource (lib "eagle-import") (part "TL36PO"))
    )
    (comp (ref "T1")
      (value "MUN2211T1-NPN_DRIVER-SC59-BEC")
      (footprint "eagle-import:SC59-BEC")
      (libsource (lib "eagle-import") (part "-NPN_DRIVER-SC59-BECMUN2211T1"))
    )
    (comp (ref "U1")
      (value "NE555DR")
      (footprint "eagle-import:SOIC127P599X175-8N")
      (fields (field (name "MF") "Texas Instruments"))
      (libsource (lib "eagle-import") (part "NE555DR"))
    )
    (comp (ref "U2")
      (value "74LVC1G11DW-7")
      (footprint "eagle-import:SOT65P210X110-6N")
      (fields (field (name "MF") "Diodes Inc."))
      (libsource (lib "eagle-import") (part "74LVC1G11DW-7"))
    )
    (comp (ref "U3")
      (value "74HC21D")
      (footprint "eagle-import:SOIC127P600X175-14N")
      (fields (field (name "MF") "Toshiba"))
      (libsource (lib "eagle-import") (part "74HC21D"))
    )
    (comp (ref "U4")
      (value "SN74AHC1G14DBVR")
      (footprint "eagle-import:SOT95P280X145-5N")
      (fields (field (name "MF") "Texas Instruments"))
      (libsource (lib "eagle-import") (part "SN74AHC1G14DBVR"))
    )
    (comp (ref "VCC")
      (value "3,81/1,4")
      (footprint "eagle-import:3,81_1,4")
      (libsource (lib "eagle-import") (part "3,81/1,4"))
    )
  )
  (nets
    (net (code "1") (name "GND") (class "Default")
      (node (ref "C1") (pin "2") (pinfunction "2_2") (pintype "passive"))
      (node (ref "C10") (pin "2") (pinfunction "2_2") (pintype "passive"))
      (node (ref "C11") (pin "2") (pinfunction "2_2") (pintype "passive"))
      (node (ref "C12") (pin "2") (pinfunction "2_2") (pintype "passive"))
      (node (ref "C13") (pin "2") (pinfunction "2_2") (pintype "passive"))
      (node (ref "C14") (pin "2") (pinfunction "2_2") (pintype "passive"))
      (node (ref "C15") (pin "2") (pinfunction "2_2") (pintype "passive"))
      (node (ref "C16") (pin "1") (pinfunction "1_1") (pintype "passive"))
      (node (ref "C17") (pin "1") (pinfunction "1_1") (pintype "passive"))
      (node (ref "C18") (pin "2") (pinfunction "2_2") (pintype "passive"))
      (node (ref "C2") (pin "2") (pinfunction "2_2") (pintype "passive"))
      (node (ref "C4") (pin "2") (pinfunction "2_2") (pintype "passive"))
      (node (ref "C5") (pin "2") (pinfunction "2_2") (pintype "passive"))
      (node (ref "C6") (pin "2") (pinfunction "2_2") (pintype "passive"))
      (node (ref "C7") (pin "2") (pinfunction "2_2") (pintype "passive"))
      (node (ref "C8") (pin "2") (pinfunction "2_2") (pintype "passive"))
      (node (ref "C9") (pin "2") (pinfunction "2_2") (pintype "passive"))
      (node (ref "D1") (pin "C") (pinfunction "C_C") (pintype "passive"))
      (node (ref "D10") (pin "C") (pinfunction "C_C") (pintype "passive"))
      (node (ref "D11") (pin "C") (pinfunction "C_C") (pintype "passive"))
      (node (ref "D12") (pin "C") (pinfunction "C_C") (pintype "passive"))
      (node (ref "D13") (pin "C") (pinfunction "C_C") (pintype "passive"))
      (node (ref "D14") (pin "C") (pinfunction "C_C") (pintype "passive"))
      (node (ref "D15") (pin "C") (pinfunction "C_C") (pintype "passive"))
      (node (ref "D16") (pin "C") (pinfunction "C_C") (pintype "passive"))
      (node (ref "D17") (pin "C") (pinfunction "C_C") (pintype "passive"))
      (node (ref "D18") (pin "C") (pinfunction "C_C") (pintype "passive"))
      (node (ref "D19") (pin "C") (pinfunction "C_C") (pintype "passive"))
      (node (ref "D2") (pin "C") (pinfunction "C_C") (pintype "passive"))
      (node (ref "D20") (pin "C") (pinfunction "C_C") (pintype "passive"))
      (node (ref "D21") (pin "C") (pinfunction "C_C") (pintype "passive"))
      (node (ref "D22") (pin "C") (pinfunction "C_C") (pintype "passive"))
      (node (ref "D23") (pin "C") (pinfunction "C_C") (pintype "passive"))
      (node (ref "D24") (pin "C") (pinfunction "C_C") (pintype "passive"))
      (node (ref "D25") (pin "C") (pinfunction "C_C") (pintype "passive"))
      (node (ref "D26") (pin "A") (pinfunction "A_A") (pintype "passive"))
      (node (ref "D3") (pin "C") (pinfunction "C_C") (pintype "passive"))
      (node (ref "D4") (pin "C") (pinfunction "C_C") (pintype "passive"))
      (node (ref "D5") (pin "C") (pinfunction "C_C") (pintype "passive"))
      (node (ref "D6") (pin "C") (pinfunction "C_C") (pintype "passive"))
      (node (ref "D7") (pin "C") (pinfunction "C_C") (pintype "passive"))
      (node (ref "D8") (pin "C") (pinfunction "C_C") (pintype "passive"))
      (node (ref "D9") (pin "C") (pinfunction "C_C") (pintype "passive"))
      (node (ref "GND") (pin "1") (pinfunction "P_1") (pintype "passive"))
      (node (ref "IC1") (pin "12") (pinfunction "GND_12") (pintype "bidirectional"))
      (node (ref "IC10") (pin "3") (pinfunction "GND_3") (pintype "power_in"))
      (node (ref "IC2") (pin "12") (pinfunction "GND_12") (pintype "bidirectional"))
      (node (ref "IC3") (pin "7") (pinfunction "GND_7") (pintype "power_in"))
      (node (ref "IC4") (pin "7") (pinfunction "GND_7") (pintype "power_in"))
      (node (ref "IC5") (pin "7") (pinfunction "GND_7") (pintype "power_in"))
      (node (ref "IC6") (pin "3") (pinfunction "GND_3") (pintype "power_in"))
      (node (ref "IC7") (pin "3") (pinfunction "GND_3") (pintype "power_in"))
      (node (ref "IC8") (pin "3") (pinfunction "GND_3") (pintype "power_in"))
      (node (ref "IC9") (pin "3") (pinfunction "GND_3") (pintype "power_in"))
      (node (ref "S1") (pin "3") (pinfunction "P_3") (pintype "passive"))
      (node (ref "U1") (pin "1") (pinfunction "GND_1") (pintype "power_in"))
      (node (ref "U2") (pin "2") (pinfunction "GND_2") (pintype "passive"))
      (node (ref "U3") (pin "7") (pinfunction "GND_7") (pintype "passive"))
      (node (ref "U4") (pin "3") (pinfunction "GND_3") (pintype "power_in"))
    )
    (net (code "2") (name "Net-(D1-PadA)") (class "Default")
      (node (ref "D1") (pin "A") (pinfunction "A_A") (pintype "passive"))
      (node (ref "R29") (pin "1") (pinfunction "1_1") (pintype "passive"))
    )
    (net (code "3") (name "Net-(D2-PadA)") (class "Default")
      (node (ref "D2") (pin "A") (pinfunction "A_A") (pintype "passive"))
      (node (ref "R30") (pin "1") (pinfunction "1_1") (pintype "passive"))
    )
    (net (code "4") (name "Net-(D3-PadA)") (class "Default")
      (node (ref "D3") (pin "A") (pinfunction "A_A") (pintype "passive"))
      (node (ref "R31") (pin "1") (pinfunction "1_1") (pintype "passive"))
    )
    (net (code "5") (name "Net-(D4-PadA)") (class "Default")
      (node (ref "D4") (pin "A") (pinfunction "A_A") (pintype "passive"))
      (node (ref "R32") (pin "1") (pinfunction "1_1") (pintype "passive"))
    )
    (net (code "6") (name "Net-(D5-PadA)") (class "Default")
      (node (ref "D5") (pin "A") (pinfunction "A_A") (pintype "passive"))
      (node (ref "R33") (pin "1") (pinfunction "1_1") (pintype "passive"))
    )
    (net (code "7") (name "Net-(D6-PadA)") (class "Default")
      (node (ref "D6") (pin "A") (pinfunction "A_A") (pintype "passive"))
      (node (ref "R34") (pin "1") (pinfunction "1_1") (pintype "passive"))
    )
    (net (code "8") (name "Net-(D7-PadA)") (class "Default")
      (node (ref "D7") (pin "A") (pinfunction "A_A") (pintype "passive"))
      (node (ref "R35") (pin "1") (pinfunction "1_1") (pintype "passive"))
    )
    (net (code "9") (name "Net-(D8-PadA)") (class "Default")
      (node (ref "D8") (pin "A") (pinfunction "A_A") (pintype "passive"))
      (node (ref "R36") (pin "1") (pinfunction "1_1") (pintype "passive"))
    )
    (net (code "10") (name "Net-(D9-PadA)") (class "Default")
      (node (ref "D9") (pin "A") (pinfunction "A_A") (pintype "passive"))
      (node (ref "R37") (pin "1") (pinfunction "1_1") (pintype "passive"))
    )
    (net (code "11") (name "Net-(D10-PadA)") (class "Default")
      (node (ref "D10") (pin "A") (pinfunction "A_A") (pintype "passive"))
      (node (ref "R38") (pin "1") (pinfunction "1_1") (pintype "passive"))
    )
    (net (code "12") (name "Net-(D11-PadA)") (class "Default")
      (node (ref "D11") (pin "A") (pinfunction "A_A") (pintype "passive"))
      (node (ref "R39") (pin "1") (pinfunction "1_1") (pintype "passive"))
    )
    (net (code "13") (name "Net-(D12-PadA)") (class "Default")
      (node (ref "D12") (pin "A") (pinfunction "A_A") (pintype "passive"))
      (node (ref "R40") (pin "1") (pinfunction "1_1") (pintype "passive"))
    )
    (net (code "14") (name "Net-(D13-PadA)") (class "Default")
      (node (ref "D13") (pin "A") (pinfunction "A_A") (pintype "passive"))
      (node (ref "R41") (pin "1") (pinfunction "1_1") (pintype "passive"))
    )
    (net (code "15") (name "Net-(D14-PadA)") (class "Default")
      (node (ref "D14") (pin "A") (pinfunction "A_A") (pintype "passive"))
      (node (ref "R42") (pin "1") (pinfunction "1_1") (pintype "passive"))
    )
    (net (code "16") (name "Net-(D15-PadA)") (class "Default")
      (node (ref "D15") (pin "A") (pinfunction "A_A") (pintype "passive"))
      (node (ref "R43") (pin "1") (pinfunction "1_1") (pintype "passive"))
    )
    (net (code "17") (name "Net-(D16-PadA)") (class "Default")
      (node (ref "D16") (pin "A") (pinfunction "A_A") (pintype "passive"))
      (node (ref "R44") (pin "1") (pinfunction "1_1") (pintype "passive"))
    )
    (net (code "18") (name "Net-(D17-PadA)") (class "Default")
      (node (ref "D17") (pin "A") (pinfunction "A_A") (pintype "passive"))
      (node (ref "R45") (pin "1") (pinfunction "1_1") (pintype "passive"))
    )
    (net (code "19") (name "Net-(D18-PadA)") (class "Default")
      (node (ref "D18") (pin "A") (pinfunction "A_A") (pintype "passive"))
      (node (ref "R46") (pin "1") (pinfunction "1_1") (pintype "passive"))
    )
    (net (code "20") (name "Net-(D19-PadA)") (class "Default")
      (node (ref "D19") (pin "A") (pinfunction "A_A") (pintype "passive"))
      (node (ref "R47") (pin "1") (pinfunction "1_1") (pintype "passive"))
    )
    (net (code "21") (name "Net-(D20-PadA)") (class "Default")
      (node (ref "D20") (pin "A") (pinfunction "A_A") (pintype "passive"))
      (node (ref "R48") (pin "1") (pinfunction "1_1") (pintype "passive"))
    )
    (net (code "22") (name "Net-(D21-PadA)") (class "Default")
      (node (ref "D21") (pin "A") (pinfunction "A_A") (pintype "passive"))
      (node (ref "R49") (pin "1") (pinfunction "1_1") (pintype "passive"))
    )
    (net (code "23") (name "Net-(D22-PadA)") (class "Default")
      (node (ref "D22") (pin "A") (pinfunction "A_A") (pintype "passive"))
      (node (ref "R50") (pin "1") (pinfunction "1_1") (pintype "passive"))
    )
    (net (code "24") (name "Net-(D23-PadA)") (class "Default")
      (node (ref "D23") (pin "A") (pinfunction "A_A") (pintype "passive"))
      (node (ref "R51") (pin "1") (pinfunction "1_1") (pintype "passive"))
    )
    (net (code "25") (name "Net-(D24-PadA)") (class "Default")
      (node (ref "D24") (pin "A") (pinfunction "A_A") (pintype "passive"))
      (node (ref "R52") (pin "1") (pinfunction "1_1") (pintype "passive"))
    )
    (net (code "26") (name "Net-(D25-PadA)") (class "Default")
      (node (ref "D25") (pin "A") (pinfunction "A_A") (pintype "passive"))
      (node (ref "R53") (pin "1") (pinfunction "1_1") (pintype "passive"))
    )
    (net (code "27") (name "Net-(IC1-A0)") (class "Default")
      (node (ref "IC1") (pin "23") (pinfunction "A0_23") (pintype "bidirectional"))
      (node (ref "IC2") (pin "23") (pinfunction "A0_23") (pintype "bidirectional"))
      (node (ref "IC4") (pin "11") (pinfunction "K_11") (pintype "input"))
      (node (ref "IC4") (pin "3") (pinfunction "Q_3") (pintype "output"))
      (node (ref "IC4") (pin "8") (pinfunction "J_8") (pintype "input"))
      (node (ref "IC6") (pin "1") (pinfunction "I0_1") (pintype "input"))
      (node (ref "U2") (pin "1") (pinfunction "A_1") (pintype "input"))
      (node (ref "U3") (pin "1") (pinfunction "1A_1") (pintype "input"))
    )
    (net (code "28") (name "Net-(IC1-A1)") (class "Default")
      (node (ref "IC1") (pin "22") (pinfunction "A1_22") (pintype "bidirectional"))
      (node (ref "IC2") (pin "22") (pinfunction "A1_22") (pintype "bidirectional"))
      (node (ref "IC4") (pin "5") (pinfunction "Q_5") (pintype "output"))
      (node (ref "IC6") (pin "2") (pinfunction "I1_2") (pintype "input"))
      (node (ref "U2") (pin "3") (pinfunction "B_3") (pintype "input"))
      (node (ref "U3") (pin "2") (pinfunction "1B_2") (pintype "input"))
    )
    (net (code "29") (name "Net-(IC1-A2)") (class "Default")
      (node (ref "IC1") (pin "21") (pinfunction "A2_21") (pintype "bidirectional"))
      (node (ref "IC2") (pin "21") (pinfunction "A2_21") (pintype "bidirectional"))
      (node (ref "IC3") (pin "3") (pinfunction "Q_3") (pintype "output"))
      (node (ref "U2") (pin "6") (pinfunction "C_6") (pintype "input"))
      (node (ref "U3") (pin "4") (pinfunction "1C_4") (pintype "input"))
    )
    (net (code "30") (name "Net-(IC1-A3)") (class "Default")
      (node (ref "IC1") (pin "20") (pinfunction "A3_20") (pintype "bidirectional"))
      (node (ref "IC2") (pin "20") (pinfunction "A3_20") (pintype "bidirectional"))
      (node (ref "IC3") (pin "5") (pinfunction "Q_5") (pintype "output"))
      (node (ref "IC7") (pin "2") (pinfunction "I1_2") (pintype "input"))
      (node (ref "U3") (pin "5") (pinfunction "1D_5") (pintype "input"))
    )
    (net (code "31") (name "Net-(IC1-VCC)") (class "Default")
      (node (ref "C10") (pin "1") (pinfunction "1_1") (pintype "passive"))
      (node (ref "C11") (pin "1") (pinfunction "1_1") (pintype "passive"))
      (node (ref "C12") (pin "1") (pinfunction "1_1") (pintype "passive"))
      (node (ref "C13") (pin "1") (pinfunction "1_1") (pintype "passive"))
      (node (ref "C14") (pin "1") (pinfunction "1_1") (pintype "passive"))
      (node (ref "C15") (pin "1") (pinfunction "1_1") (pintype "passive"))
      (node (ref "C16") (pin "2") (pinfunction "2_2") (pintype "passive"))
      (node (ref "C17") (pin "2") (pinfunction "2_2") (pintype "passive"))
      (node (ref "C18") (pin "1") (pinfunction "1_1") (pintype "passive"))
      (node (ref "C3") (pin "1") (pinfunction "1_1") (pintype "passive"))
      (node (ref "C6") (pin "1") (pinfunction "1_1") (pintype "passive"))
      (node (ref "C7") (pin "1") (pinfunction "1_1") (pintype "passive"))
      (node (ref "C8") (pin "1") (pinfunction "1_1") (pintype "passive"))
      (node (ref "C9") (pin "1") (pinfunction "1_1") (pintype "passive"))
      (node (ref "D26") (pin "C") (pinfunction "C_C") (pintype "passive"))
      (node (ref "F") (pin "2") (pinfunction "2_2") (pintype "passive"))
      (node (ref "IC1") (pin "24") (pinfunction "VCC_24") (pintype "bidirectional"))
      (node (ref "IC10") (pin "5") (pinfunction "VCC_5") (pintype "power_in"))
      (node (ref "IC2") (pin "24") (pinfunction "VCC_24") (pintype "bidirectional"))
      (node (ref "IC3") (pin "14") (pinfunction "VCC_14") (pintype "power_in"))
      (node (ref "IC4") (pin "14") (pinfunction "VCC_14") (pintype "power_in"))
      (node (ref "IC5") (pin "14") (pinfunction "VCC_14") (pintype "power_in"))
      (node (ref "IC6") (pin "5") (pinfunction "VCC_5") (pintype "power_in"))
      (node (ref "IC7") (pin "5") (pinfunction "VCC_5") (pintype "power_in"))
      (node (ref "IC8") (pin "5") (pinfunction "VCC_5") (pintype "power_in"))
      (node (ref "IC9") (pin "5") (pinfunction "VCC_5") (pintype "power_in"))
      (node (ref "Q1") (pin "3") (pinfunction "D_3") (pintype "passive"))
      (node (ref "Q10") (pin "3") (pinfunction "D_3") (pintype "passive"))
      (node (ref "Q11") (pin "3") (pinfunction "D_3") (pintype "passive"))
      (node (ref "Q12") (pin "3") (pinfunction "D_3") (pintype "passive"))
      (node (ref "Q13") (pin "3") (pinfunction "D_3") (pintype "passive"))
      (node (ref "Q14") (pin "3") (pinfunction "D_3") (pintype "passive"))
      (node (ref "Q15") (pin "3") (pinfunction "D_3") (pintype "passive"))
      (node (ref "Q16") (pin "3") (pinfunction "D_3") (pintype "passive"))
      (node (ref "Q17") (pin "3") (pinfunction "D_3") (pintype "passive"))
      (node (ref "Q18") (pin "3") (pinfunction "D_3") (pintype "passive"))
      (node (ref "Q19") (pin "3") (pinfunction "D_3") (pintype "passive"))
      (node (ref "Q2") (pin "3") (pinfunction "D_3") (pintype "passive"))
      (node (ref "Q20") (pin "3") (pinfunction "D_3") (pintype "passive"))
      (node (ref "Q21") (pin "3") (pinfunction "D_3") (pintype "passive"))
      (node (ref "Q22") (pin "3") (pinfunction "D_3") (pintype "passive"))
      (node (ref "Q23") (pin "3") (pinfunction "D_3") (pintype "passive"))
      (node (ref "Q24") (pin "3") (pinfunction "D_3") (pintype "passive"))
      (node (ref "Q25") (pin "3") (pinfunction "D_3") (pintype "passive"))
      (node (ref "Q3") (pin "3") (pinfunction "D_3") (pintype "passive"))
      (node (ref "Q4") (pin "3") (pinfunction "D_3") (pintype "passive"))
      (node (ref "Q5") (pin "3") (pinfunction "D_3") (pintype "passive"))
      (node (ref "Q6") (pin "3") (pinfunction "D_3") (pintype "passive"))
      (node (ref "Q7") (pin "3") (pinfunction "D_3") (pintype "passive"))
      (node (ref "Q8") (pin "3") (pinfunction "D_3") (pintype "passive"))
      (node (ref "Q9") (pin "3") (pinfunction "D_3") (pintype "passive"))
      (node (ref "S4") (pin "3") (pinfunction "S_3") (pintype "passive"))
      (node (ref "T1") (pin "C") (pinfunction "C_C") (pintype "passive"))
      (node (ref "U1") (pin "4") (pinfunction "RESET_4") (pintype "input"))
      (node (ref "U2") (pin "5") (pinfunction "VCC_5") (pintype "power_in"))
      (node (ref "U3") (pin "14") (pinfunction "VCC_14") (pintype "power_in"))
      (node (ref "U4") (pin "5") (pinfunction "VCC_5") (pintype "power_in"))
    )
    (net (code "32") (name "Net-(IC1-~{E0})") (class "Default")
      (node (ref "IC1") (pin "18") (pinfunction "~{E0}_18") (pintype "bidirectional"))
      (node (ref "IC1") (pin "19") (pinfunction "~{E1}_19") (pintype "bidirectional"))
      (node (ref "IC5") (pin "3") (pinfunction "Q_3") (pintype "output"))
      (node (ref "IC7") (pin "1") (pinfunction "I0_1") (pintype "input"))
      (node (ref "U4") (pin "2") (pinfunction "A_2") (pintype "input"))
    )
    (net (code "33") (name "Net-(IC1-~{Y0})") (class "Default")
      (node (ref "IC1") (pin "1") (pinfunction "~{Y0}_1") (pintype "bidirectional"))
      (node (ref "R4") (pin "1") (pinfunction "1_1") (pintype "passive"))
    )
    (net (code "34") (name "Net-(IC1-~{Y1})") (class "Default")
      (node (ref "IC1") (pin "2") (pinfunction "~{Y1}_2") (pintype "bidirectional"))
      (node (ref "R5") (pin "1") (pinfunction "1_1") (pintype "passive"))
    )
    (net (code "35") (name "Net-(IC1-~{Y2})") (class "Default")
      (node (ref "IC1") (pin "3") (pinfunction "~{Y2}_3") (pintype "bidirectional"))
      (node (ref "R6") (pin "1") (pinfunction "1_1") (pintype "passive"))
    )
    (net (code "36") (name "Net-(IC1-~{Y3})") (class "Default")
      (node (ref "IC1") (pin "4") (pinfunction "~{Y3}_4") (pintype "bidirectional"))
      (node (ref "R7") (pin "1") (pinfunction "1_1") (pintype "passive"))
    )
    (net (code "37") (name "Net-(IC1-~{Y4})") (class "Default")
      (node (ref "IC1") (pin "5") (pinfunction "~{Y4}_5") (pintype "bidirectional"))
      (node (ref "R8") (pin "1") (pinfunction "1_1") (pintype "passive"))
    )
    (net (code "38") (name "Net-(IC1-~{Y5})") (class "Default")
      (node (ref "IC1") (pin "6") (pinfunction "~{Y5}_6") (pintype "bidirectional"))
      (node (ref "R9") (pin "1") (pinfunction "1_1") (pintype "passive"))
    )
    (net (code "39") (name "Net-(IC1-~{Y6})") (class "Default")
      (node (ref "IC1") (pin "7") (pinfunction "~{Y6}_7") (pintype "bidirectional"))
      (node (ref "R10") (pin "1") (pinfunction "1_1") (pintype "passive"))
    )
    (net (code "40") (name "Net-(IC1-~{Y7})") (class "Default")
      (node (ref "IC1") (pin "8") (pinfunction "~{Y7}_8") (pintype "bidirectional"))
      (node (ref "R11") (pin "1") (pinfunction "1_1") (pintype "passive"))
    )
    (net (code "41") (name "Net-(IC1-~{Y8})") (class "Default")
      (node (ref "IC1") (pin "9") (pinfunction "~{Y8}_9") (pintype "bidirectional"))
      (node (ref "R12") (pin "1") (pinfunction "1_1") (pintype "passive"))
    )
    (net (code "42") (name "Net-(IC1-~{Y9})") (class "Default")
      (node (ref "IC1") (pin "10") (pinfunction "~{Y9}_10") (pintype "bidirectional"))
      (node (ref "R13") (pin "1") (pinfunction "1_1") (pintype "passive"))
    )
    (net (code "43") (name "Net-(IC1-~{Y10})") (class "Default")
      (node (ref "IC1") (pin "11") (pinfunction "~{Y10}_11") (pintype "bidirectional"))
      (node (ref "R14") (pin "1") (pinfunction "1_1") (pintype "passive"))
      (node (ref "S4") (pin "1") (pinfunction "O_1") (pintype "passive"))
    )
    (net (code "44") (name "Net-(IC1-~{Y11})") (class "Default")
      (node (ref "IC1") (pin "13") (pinfunction "~{Y11}_13") (pintype "bidirectional"))
      (node (ref "R15") (pin "1") (pinfunction "1_1") (pintype "passive"))
    )
    (net (code "45") (name "Net-(IC1-~{Y12})") (class "Default")
      (node (ref "IC1") (pin "14") (pinfunction "~{Y12}_14") (pintype "bidirectional"))
      (node (ref "R16") (pin "1") (pinfunction "1_1") (pintype "passive"))
    )
    (net (code "46") (name "Net-(IC1-~{Y13})") (class "Default")
      (node (ref "IC1") (pin "15") (pinfunction "~{Y13}_15") (pintype "bidirectional"))
      (node (ref "R17") (pin "1") (pinfunction "1_1") (pintype "passive"))
    )
    (net (code "47") (name "Net-(IC1-~{Y14})") (class "Default")
      (node (ref "IC1") (pin "16") (pinfunction "~{Y14}_16") (pintype "bidirectional"))
      (node (ref "R18") (pin "1") (pinfunction "1_1") (pintype "passive"))
    )
    (net (code "48") (name "Net-(IC1-~{Y15})") (class "Default")
      (node (ref "IC1") (pin "17") (pinfunction "~{Y15}_17") (pintype "bidirectional"))
      (node (ref "R19") (pin "1") (pinfunction "1_1") (pintype "passive"))
    )
    (net (code "49") (name "Net-(IC2-~{E0})") (class "Default")
      (node (ref "IC2") (pin "18") (pinfunction "~{E0}_18") (pintype "bidirectional"))
      (node (ref "IC2") (pin "19") (pinfunction "~{E1}_19") (pintype "bidirectional"))
      (node (ref "U4") (pin "4") (pinfunction "Y_4") (pintype "output"))
    )
    (net (code "50") (name "Net-(IC2-~{Y0})") (class "Default")
      (node (ref "IC2") (pin "1") (pinfunction "~{Y0}_1") (pintype "bidirectional"))
      (node (ref "R20") (pin "1") (pinfunction "1_1") (pintype "passive"))
    )
    (net (code "51") (name "Net-(IC2-~{Y1})") (class "Default")
      (node (ref "IC2") (pin "2") (pinfunction "~{Y1}_2") (pintype "bidirectional"))
      (node (ref "R21") (pin "1") (pinfunction "1_1") (pintype "passive"))
    )
    (net (code "52") (name "Net-(IC2-~{Y2})") (class "Default")
      (node (ref "IC2") (pin "3") (pinfunction "~{Y2}_3") (pintype "bidirectional"))
      (node (ref "R22") (pin "1") (pinfunction "1_1") (pintype "passive"))
    )
    (net (code "53") (name "Net-(IC2-~{Y3})") (class "Default")
      (node (ref "IC2") (pin "4") (pinfunction "~{Y3}_4") (pintype "bidirectional"))
      (node (ref "R23") (pin "1") (pinfunction "1_1") (pintype "passive"))
    )
    (net (code "54") (name "Net-(IC2-~{Y4})") (class "Default")
      (node (ref "IC2") (pin "5") (pinfunction "~{Y4}_5") (pintype "bidirectional"))
      (node (ref "R24") (pin "1") (pinfunction "1_1") (pintype "passive"))
    )
    (net (code "55") (name "Net-(IC2-~{Y5})") (class "Default")
      (node (ref "IC2") (pin "6") (pinfunction "~{Y5}_6") (pintype "bidirectional"))
      (node (ref "R25") (pin "1") (pinfunction "1_1") (pintype "passive"))
    )
    (net (code "56") (name "Net-(IC2-~{Y6})") (class "Default")
      (node (ref "IC2") (pin "7") (pinfunction "~{Y6}_7") (pintype "bidirectional"))
      (node (ref "R26") (pin "1") (pinfunction "1_1") (pintype "passive"))
    )
    (net (code "57") (name "Net-(IC2-~{Y7})") (class "Default")
      (node (ref "IC2") (pin "8") (pinfunction "~{Y7}_8") (pintype "bidirectional"))
      (node (ref "R27") (pin "1") (pinfunction "1_1") (pintype "passive"))
    )
    (net (code "58") (name "Net-(IC2-~{Y8})") (class "Default")
      (node (ref "IC2") (pin "9") (pinfunction "~{Y8}_9") (pintype "bidirectional"))
      (node (ref "R28") (pin "1") (pinfunction "1_1") (pintype "passive"))
    )
    (net (code "59") (name "Net-(IC3A-CLK)") (class "Default")
      (node (ref "IC3") (pin "12") (pinfunction "CLK_12") (pintype "input"))
      (node (ref "IC3") (pin "9") (pinfunction "CLK_9") (pintype "input"))
      (node (ref "IC4") (pin "12") (pinfunction "CLK_12") (pintype "input"))
      (node (ref "IC4") (pin "9") (pinfunction "CLK_9") (pintype "input"))
      (node (ref "IC5") (pin "12") (pinfunction "CLK_12") (pintype "input"))
      (node (ref "U1") (pin "3") (pinfunction "OUT_3") (pintype "output"))
    )
    (net (code "60") (name "Net-(IC3A-CLR)") (class "Default")
      (node (ref "C5") (pin "1") (pinfunction "1_1") (pintype "passive"))
      (node (ref "IC3") (pin "10") (pinfunction "CLR_10") (pintype "input"))
      (node (ref "IC3") (pin "13") (pinfunction "CLR_13") (pintype "input"))
      (node (ref "IC4") (pin "10") (pinfunction "CLR_10") (pintype "input"))
      (node (ref "IC4") (pin "13") (pinfunction "CLR_13") (pintype "input"))
      (node (ref "IC5") (pin "13") (pinfunction "CLR_13") (pintype "input"))
      (node (ref "S1") (pin "1") (pinfunction "S_1") (pintype "passive"))
      (node (ref "T1") (pin "E") (pinfunction "E_E") (pintype "passive"))
    )
    (net (code "61") (name "Net-(IC3A-J)") (class "Default")
      (node (ref "IC3") (pin "1") (pinfunction "J_1") (pintype "input"))
      (node (ref "IC3") (pin "4") (pinfunction "K_4") (pintype "input"))
      (node (ref "IC6") (pin "4") (pinfunction "O_4") (pintype "output"))
    )
    (net (code "62") (name "Net-(IC3B-J)") (class "Default")
      (node (ref "IC3") (pin "11") (pinfunction "K_11") (pintype "input"))
      (node (ref "IC3") (pin "8") (pinfunction "J_8") (pintype "input"))
      (node (ref "IC9") (pin "4") (pinfunction "O_4") (pintype "output"))
    )
    (net (code "63") (name "Net-(IC5A-J)") (class "Default")
      (node (ref "IC5") (pin "1") (pinfunction "J_1") (pintype "input"))
      (node (ref "IC5") (pin "4") (pinfunction "K_4") (pintype "input"))
      (node (ref "IC8") (pin "4") (pinfunction "O_4") (pintype "output"))
    )
    (net (code "64") (name "Net-(IC7A-O)") (class "Default")
      (node (ref "IC7") (pin "4") (pinfunction "O_4") (pintype "output"))
      (node (ref "IC8") (pin "2") (pinfunction "I1_2") (pintype "input"))
      (node (ref "IC9") (pin "2") (pinfunction "I1_2") (pintype "input"))
    )
    (net (code "65") (name "Net-(IC8A-I0)") (class "Default")
      (node (ref "IC8") (pin "1") (pinfunction "I0_1") (pintype "input"))
      (node (ref "U3") (pin "6") (pinfunction "1Y_6") (pintype "output"))
    )
    (net (code "66") (name "Net-(IC9A-I0)") (class "Default")
      (node (ref "IC9") (pin "1") (pinfunction "I0_1") (pintype "input"))
      (node (ref "U2") (pin "4") (pinfunction "Y_4") (pintype "output"))
    )
    (net (code "67") (name "Net-(IC10A-I0)") (class "Default")
      (node (ref "IC10") (pin "1") (pinfunction "I0_1") (pintype "input"))
      (node (ref "IC5") (pin "2") (pinfunction "~{Q}_2") (pintype "output"))
    )
    (net (code "68") (name "Net-(IC10A-I1)") (class "Default")
      (node (ref "IC10") (pin "2") (pinfunction "I1_2") (pintype "input"))
      (node (ref "IC3") (pin "6") (pinfunction "~{Q}_6") (pintype "output"))
    )
    (net (code "69") (name "Net-(IC10A-O)") (class "Default")
      (node (ref "IC10") (pin "4") (pinfunction "O_4") (pintype "output"))
      (node (ref "IC4") (pin "1") (pinfunction "J_1") (pintype "input"))
      (node (ref "IC4") (pin "4") (pinfunction "K_4") (pintype "input"))
    )
    (net (code "70") (name "Net-(J1-CC1)") (class "Default")
      (node (ref "J1") (pin "A5") (pinfunction "CC1_A5") (pintype "bidirectional"))
      (node (ref "J3") (pin "5") (pinfunction "STDA_SSRX-_5") (pintype "bidirectional"))
      (node (ref "Q5") (pin "2") (pinfunction "S_2") (pintype "passive"))
    )
    (net (code "71") (name "Net-(J1-CC2)") (class "Default")
      (node (ref "J1") (pin "B5") (pinfunction "CC2_B5") (pintype "bidirectional"))
      (node (ref "Q17") (pin "2") (pinfunction "S_2") (pintype "passive"))
    )
    (net (code "72") (name "Net-(J1-DN1)") (class "Default")
      (node (ref "J1") (pin "A7") (pinfunction "DN1_A7") (pintype "bidirectional"))
      (node (ref "J3") (pin "7") (pinfunction "GND_DRAIN_7") (pintype "power_in"))
      (node (ref "Q7") (pin "2") (pinfunction "S_2") (pintype "passive"))
    )
    (net (code "73") (name "Net-(J1-DN2)") (class "Default")
      (node (ref "J1") (pin "B7") (pinfunction "DN2_B7") (pintype "bidirectional"))
      (node (ref "Q19") (pin "2") (pinfunction "S_2") (pintype "passive"))
    )
    (net (code "74") (name "Net-(J1-DP1)") (class "Default")
      (node (ref "J1") (pin "A6") (pinfunction "DP1_A6") (pintype "bidirectional"))
      (node (ref "J3") (pin "6") (pinfunction "STDA_SSRX+_6") (pintype "bidirectional"))
      (node (ref "Q6") (pin "2") (pinfunction "S_2") (pintype "passive"))
    )
    (net (code "75") (name "Net-(J1-DP2)") (class "Default")
      (node (ref "J1") (pin "B6") (pinfunction "DP2_B6") (pintype "bidirectional"))
      (node (ref "Q18") (pin "2") (pinfunction "S_2") (pintype "passive"))
    )
    (net (code "76") (name "Net-(J1-SBU1)") (class "Default")
      (node (ref "J1") (pin "A8") (pinfunction "SBU1_A8") (pintype "bidirectional"))
      (node (ref "J3") (pin "8") (pinfunction "STDA_SSTX-_8") (pintype "bidirectional"))
      (node (ref "Q8") (pin "2") (pinfunction "S_2") (pintype "passive"))
    )
    (net (code "77") (name "Net-(J1-SBU2)") (class "Default")
      (node (ref "J1") (pin "B8") (pinfunction "SBU2_B8") (pintype "bidirectional"))
      (node (ref "Q20") (pin "2") (pinfunction "S_2") (pintype "passive"))
    )
    (net (code "78") (name "Net-(J1-SSRXN1)") (class "Default")
      (node (ref "J1") (pin "B10") (pinfunction "SSRXN1_B10") (pintype "bidirectional"))
      (node (ref "Q22") (pin "2") (pinfunction "S_2") (pintype "passive"))
    )
    (net (code "79") (name "Net-(J1-SSRXN2)") (class "Default")
      (node (ref "J1") (pin "A10") (pinfunction "SSRXN2_A10") (pintype "bidirectional"))
      (node (ref "J3") (pin "S1") (pinfunction "SHIELD_S1") (pintype "passive"))
      (node (ref "J3") (pin "S2") (pinfunction "SHIELD_S2") (pintype "passive"))
      (node (ref "J3") (pin "S3") (pinfunction "SHIELD_S3") (pintype "passive"))
      (node (ref "J3") (pin "S4") (pinfunction "SHIELD_S4") (pintype "passive"))
      (node (ref "Q10") (pin "2") (pinfunction "S_2") (pintype "passive"))
    )
    (net (code "80") (name "Net-(J1-SSRXP1)") (class "Default")
      (node (ref "J1") (pin "B11") (pinfunction "SSRXP1_B11") (pintype "bidirectional"))
      (node (ref "Q23") (pin "2") (pinfunction "S_2") (pintype "passive"))
    )
    (net (code "81") (name "Net-(J1-SSRXP2)") (class "Default")
      (node (ref "J1") (pin "A11") (pinfunction "SSRXP2_A11") (pintype "bidirectional"))
      (node (ref "Q11") (pin "2") (pinfunction "S_2") (pintype "passive"))
    )
    (net (code "82") (name "Net-(J1-SSTXN1)") (class "Default")
      (node (ref "J1") (pin "A3") (pinfunction "SSTXN1_A3") (pintype "bidirectional"))
      (node (ref "J3") (pin "3") (pinfunction "D+_3") (pintype "bidirectional"))
      (node (ref "Q3") (pin "2") (pinfunction "S_2") (pintype "passive"))
    )
    (net (code "83") (name "Net-(J1-SSTXN2)") (class "Default")
      (node (ref "J1") (pin "B3") (pinfunction "SSTXN2_B3") (pintype "bidirectional"))
      (node (ref "Q15") (pin "2") (pinfunction "S_2") (pintype "passive"))
    )
    (net (code "84") (name "Net-(J1-SSTXP1)") (class "Default")
      (node (ref "J1") (pin "A2") (pinfunction "SSTXP1_A2") (pintype "bidirectional"))
      (node (ref "J3") (pin "2") (pinfunction "D-_2") (pintype "bidirectional"))
      (node (ref "Q2") (pin "2") (pinfunction "S_2") (pintype "passive"))
    )
    (net (code "85") (name "Net-(J1-SSTXP2)") (class "Default")
      (node (ref "J1") (pin "B2") (pinfunction "SSTXP2_B2") (pintype "bidirectional"))
      (node (ref "Q14") (pin "2") (pinfunction "S_2") (pintype "passive"))
    )
    (net (code "86") (name "Net-(J2-CC1)") (class "Default")
      (node (ref "J2") (pin "A5") (pinfunction "CC1_A5") (pintype "bidirectional"))
      (node (ref "R33") (pin "2") (pinfunction "2_2") (pintype "passive"))
    )
    (net (code "87") (name "Net-(J2-CC2)") (class "Default")
      (node (ref "J2") (pin "B5") (pinfunction "CC2_B5") (pintype "bidirectional"))
      (node (ref "R45") (pin "2") (pinfunction "2_2") (pintype "passive"))
    )
    (net (code "88") (name "Net-(J2-DN1)") (class "Default")
      (node (ref "J2") (pin "A7") (pinfunction "DN1_A7") (pintype "bidirectional"))
      (node (ref "R35") (pin "2") (pinfunction "2_2") (pintype "passive"))
    )
    (net (code "89") (name "Net-(J2-DN2)") (class "Default")
      (node (ref "J2") (pin "B7") (pinfunction "DN2_B7") (pintype "bidirectional"))
      (node (ref "R47") (pin "2") (pinfunction "2_2") (pintype "passive"))
    )
    (net (code "90") (name "Net-(J2-DP1)") (class "Default")
      (node (ref "J2") (pin "A6") (pinfunction "DP1_A6") (pintype "bidirectional"))
      (node (ref "R34") (pin "2") (pinfunction "2_2") (pintype "passive"))
    )
    (net (code "91") (name "Net-(J2-DP2)") (class "Default")
      (node (ref "J2") (pin "B6") (pinfunction "DP2_B6") (pintype "bidirectional"))
      (node (ref "R46") (pin "2") (pinfunction "2_2") (pintype "passive"))
    )
    (net (code "92") (name "Net-(J2-GND_A-PadA1)") (class "Default")
      (node (ref "J2") (pin "A1") (pinfunction "GND_A_A1") (pintype "power_in"))
      (node (ref "J2") (pin "A12") (pinfunction "GND_A_A12") (pintype "power_in"))
      (node (ref "R29") (pin "2") (pinfunction "2_2") (pintype "passive"))
      (node (ref "R40") (pin "2") (pinfunction "2_2") (pintype "passive"))
    )
    (net (code "93") (name "Net-(J2-GND_B-PadB1)") (class "Default")
      (node (ref "J2") (pin "B1") (pinfunction "GND_B_B1") (pintype "power_in"))
      (node (ref "J2") (pin "B12") (pinfunction "GND_B_B12") (pintype "power_in"))
      (node (ref "R41") (pin "2") (pinfunction "2_2") (pintype "passive"))
      (node (ref "R52") (pin "2") (pinfunction "2_2") (pintype "passive"))
    )
    (net (code "94") (name "Net-(J2-SBU1)") (class "Default")
      (node (ref "J2") (pin "A8") (pinfunction "SBU1_A8") (pintype "bidirectional"))
      (node (ref "R36") (pin "2") (pinfunction "2_2") (pintype "passive"))
    )
    (net (code "95") (name "Net-(J2-SBU2)") (class "Default")
      (node (ref "J2") (pin "B8") (pinfunction "SBU2_B8") (pintype "bidirectional"))
      (node (ref "R48") (pin "2") (pinfunction "2_2") (pintype "passive"))
    )
    (net (code "96") (name "Net-(J2-SHELL_GND-PadS1)") (class "Default")
      (node (ref "J2") (pin "S1") (pinfunction "SHELL_GND_S1") (pintype "power_in"))
      (node (ref "J2") (pin "S2") (pinfunction "SHELL_GND_S2") (pintype "power_in"))
      (node (ref "J2") (pin "S3") (pinfunction "SHELL_GND_S3") (pintype "power_in"))
      (node (ref "J2") (pin "S4") (pinfunction "SHELL_GND_S4") (pintype "power_in"))
      (node (ref "R53") (pin "2") (pinfunction "2_2") (pintype "passive"))
    )
    (net (code "97") (name "Net-(J2-SSRXN1)") (class "Default")
      (node (ref "J2") (pin "B10") (pinfunction "SSRXN1_B10") (pintype "bidirectional"))
      (node (ref "R50") (pin "2") (pinfunction "2_2") (pintype "passive"))
    )
    (net (code "98") (name "Net-(J2-SSRXN2)") (class "Default")
      (node (ref "J2") (pin "A10") (pinfunction "SSRXN2_A10") (pintype "bidirectional"))
      (node (ref "R38") (pin "2") (pinfunction "2_2") (pintype "passive"))
    )
    (net (code "99") (name "Net-(J2-SSRXP1)") (class "Default")
      (node (ref "J2") (pin "B11") (pinfunction "SSRXP1_B11") (pintype "bidirectional"))
      (node (ref "R51") (pin "2") (pinfunction "2_2") (pintype "passive"))
    )
    (net (code "100") (name "Net-(J2-SSRXP2)") (class "Default")
      (node (ref "J2") (pin "A11") (pinfunction "SSRXP2_A11") (pintype "bidirectional"))
      (node (ref "R39") (pin "2") (pinfunction "2_2") (pintype "passive"))
    )
    (net (code "101") (name "Net-(J2-SSTXN1)") (class "Default")
      (node (ref "J2") (pin "A3") (pinfunction "SSTXN1_A3") (pintype "bidirectional"))
      (node (ref "R31") (pin "2") (pinfunction "2_2") (pintype "passive"))
    )
    (net (code "102") (name "Net-(J2-SSTXN2)") (class "Default")
      (node (ref "J2") (pin "B3") (pinfunction "SSTXN2_B3") (pintype "bidirectional"))
      (node (ref "R43") (pin "2") (pinfunction "2_2") (pintype "passive"))
    )
    (net (code "103") (name "Net-(J2-SSTXP1)") (class "Default")
      (node (ref "J2") (pin "A2") (pinfunction "SSTXP1_A2") (pintype "bidirectional"))
      (node (ref "R30") (pin "2") (pinfunction "2_2") (pintype "passive"))
    )
    (net (code "104") (name "Net-(J2-SSTXP2)") (class "Default")
      (node (ref "J2") (pin "B2") (pinfunction "SSTXP2_B2") (pintype "bidirectional"))
      (node (ref "R42") (pin "2") (pinfunction "2_2") (pintype "passive"))
    )
    (net (code "105") (name "Net-(J2-VBUS_A-PadA4)") (class "Default")
      (node (ref "J2") (pin "A4") (pinfunction "VBUS_A_A4") (pintype "power_in"))
      (node (ref "J2") (pin "A9") (pinfunction "VBUS_A_A9") (pintype "power_in"))
      (node (ref "R32") (pin "2") (pinfunction "2_2") (pintype "passive"))
      (node (ref "R37") (pin "2") (pinfunction "2_2") (pintype "passive"))
    )
    (net (code "106") (name "Net-(J2-VBUS_B-PadB4)") (class "Default")
      (node (ref "J2") (pin "B4") (pinfunction "VBUS_B_B4") (pintype "power_in"))
      (node (ref "J2") (pin "B9") (pinfunction "VBUS_B_B9") (pintype "power_in"))
      (node (ref "R44") (pin "2") (pinfunction "2_2") (pintype "passive"))
      (node (ref "R49") (pin "2") (pinfunction "2_2") (pintype "passive"))
    )
    (net (code "107") (name "Net-(J3-GND)") (class "Default")
      (node (ref "J1") (pin "A4") (pinfunction "VBUS_A_A4") (pintype "power_in"))
      (node (ref "J1") (pin "A9") (pinfunction "VBUS_A_A9") (pintype "power_in"))
      (node (ref "J3") (pin "4") (pinfunction "GND_4") (pintype "power_in"))
      (node (ref "J3") (pin "9") (pinfunction "STDA_SSTX+_9") (pintype "bidirectional"))
      (node (ref "Q4") (pin "2") (pinfunction "S_2") (pintype "passive"))
      (node (ref "Q9") (pin "2") (pinfunction "S_2") (pintype "passive"))
    )
    (net (code "108") (name "Net-(J3-VBUS)") (class "Default")
      (node (ref "J1") (pin "A1") (pinfunction "GND_A_A1") (pintype "power_in"))
      (node (ref "J1") (pin "A12") (pinfunction "GND_A_A12") (pintype "power_in"))
      (node (ref "J3") (pin "1") (pinfunction "VBUS_1") (pintype "power_in"))
      (node (ref "Q1") (pin "2") (pinfunction "S_2") (pintype "passive"))
      (node (ref "Q12") (pin "2") (pinfunction "S_2") (pintype "passive"))
    )
    (net (code "109") (name "Net-(Q1-G)") (class "Default")
      (node (ref "Q1") (pin "1") (pinfunction "G_1") (pintype "passive"))
      (node (ref "R4") (pin "2") (pinfunction "2_2") (pintype "passive"))
    )
    (net (code "110") (name "Net-(Q2-G)") (class "Default")
      (node (ref "Q2") (pin "1") (pinfunction "G_1") (pintype "passive"))
      (node (ref "R5") (pin "2") (pinfunction "2_2") (pintype "passive"))
    )
    (net (code "111") (name "Net-(Q3-G)") (class "Default")
      (node (ref "Q3") (pin "1") (pinfunction "G_1") (pintype "passive"))
      (node (ref "R6") (pin "2") (pinfunction "2_2") (pintype "passive"))
    )
    (net (code "112") (name "Net-(Q4-G)") (class "Default")
      (node (ref "Q4") (pin "1") (pinfunction "G_1") (pintype "passive"))
      (node (ref "R7") (pin "2") (pinfunction "2_2") (pintype "passive"))
    )
    (net (code "113") (name "Net-(Q5-G)") (class "Default")
      (node (ref "Q5") (pin "1") (pinfunction "G_1") (pintype "passive"))
      (node (ref "R8") (pin "2") (pinfunction "2_2") (pintype "passive"))
    )
    (net (code "114") (name "Net-(Q6-G)") (class "Default")
      (node (ref "Q6") (pin "1") (pinfunction "G_1") (pintype "passive"))
      (node (ref "R9") (pin "2") (pinfunction "2_2") (pintype "passive"))
    )
    (net (code "115") (name "Net-(Q7-G)") (class "Default")
      (node (ref "Q7") (pin "1") (pinfunction "G_1") (pintype "passive"))
      (node (ref "R10") (pin "2") (pinfunction "2_2") (pintype "passive"))
    )
    (net (code "116") (name "Net-(Q8-G)") (class "Default")
      (node (ref "Q8") (pin "1") (pinfunction "G_1") (pintype "passive"))
      (node (ref "R11") (pin "2") (pinfunction "2_2") (pintype "passive"))
    )
    (net (code "117") (name "Net-(Q9-G)") (class "Default")
      (node (ref "Q9") (pin "1") (pinfunction "G_1") (pintype "passive"))
      (node (ref "R12") (pin "2") (pinfunction "2_2") (pintype "passive"))
    )
    (net (code "118") (name "Net-(Q10-G)") (class "Default")
      (node (ref "Q10") (pin "1") (pinfunction "G_1") (pintype "passive"))
      (node (ref "R13") (pin "2") (pinfunction "2_2") (pintype "passive"))
    )
    (net (code "119") (name "Net-(Q11-G)") (class "Default")
      (node (ref "Q11") (pin "1") (pinfunction "G_1") (pintype "passive"))
      (node (ref "R14") (pin "2") (pinfunction "2_2") (pintype "passive"))
    )
    (net (code "120") (name "Net-(Q12-G)") (class "Default")
      (node (ref "Q12") (pin "1") (pinfunction "G_1") (pintype "passive"))
      (node (ref "R15") (pin "2") (pinfunction "2_2") (pintype "passive"))
    )
    (net (code "121") (name "Net-(Q13-G)") (class "Default")
      (node (ref "Q13") (pin "1") (pinfunction "G_1") (pintype "passive"))
      (node (ref "R16") (pin "2") (pinfunction "2_2") (pintype "passive"))
    )
    (net (code "122") (name "Net-(Q13-S)") (class "Default")
      (node (ref "J1") (pin "B1") (pinfunction "GND_B_B1") (pintype "power_in"))
      (node (ref "J1") (pin "B12") (pinfunction "GND_B_B12") (pintype "power_in"))
      (node (ref "Q13") (pin "2") (pinfunction "S_2") (pintype "passive"))
      (node (ref "Q24") (pin "2") (pinfunction "S_2") (pintype "passive"))
    )
    (net (code "123") (name "Net-(Q14-G)") (class "Default")
      (node (ref "Q14") (pin "1") (pinfunction "G_1") (pintype "passive"))
      (node (ref "R17") (pin "2") (pinfunction "2_2") (pintype "passive"))
    )
    (net (code "124") (name "Net-(Q15-G)") (class "Default")
      (node (ref "Q15") (pin "1") (pinfunction "G_1") (pintype "passive"))
      (node (ref "R18") (pin "2") (pinfunction "2_2") (pintype "passive"))
    )
    (net (code "125") (name "Net-(Q16-G)") (class "Default")
      (node (ref "Q16") (pin "1") (pinfunction "G_1") (pintype "passive"))
      (node (ref "R19") (pin "2") (pinfunction "2_2") (pintype "passive"))
    )
    (net (code "126") (name "Net-(Q16-S)") (class "Default")
      (node (ref "J1") (pin "B4") (pinfunction "VBUS_B_B4") (pintype "power_in"))
      (node (ref "J1") (pin "B9") (pinfunction "VBUS_B_B9") (pintype "power_in"))
      (node (ref "Q16") (pin "2") (pinfunction "S_2") (pintype "passive"))
      (node (ref "Q21") (pin "2") (pinfunction "S_2") (pintype "passive"))
    )
    (net (code "127") (name "Net-(Q17-G)") (class "Default")
      (node (ref "Q17") (pin "1") (pinfunction "G_1") (pintype "passive"))
      (node (ref "R20") (pin "2") (pinfunction "2_2") (pintype "passive"))
    )
    (net (code "128") (name "Net-(Q18-G)") (class "Default")
      (node (ref "Q18") (pin "1") (pinfunction "G_1") (pintype "passive"))
      (node (ref "R21") (pin "2") (pinfunction "2_2") (pintype "passive"))
    )
    (net (code "129") (name "Net-(Q19-G)") (class "Default")
      (node (ref "Q19") (pin "1") (pinfunction "G_1") (pintype "passive"))
      (node (ref "R22") (pin "2") (pinfunction "2_2") (pintype "passive"))
    )
    (net (code "130") (name "Net-(Q20-G)") (class "Default")
      (node (ref "Q20") (pin "1") (pinfunction "G_1") (pintype "passive"))
      (node (ref "R23") (pin "2") (pinfunction "2_2") (pintype "passive"))
    )
    (net (code "131") (name "Net-(Q21-G)") (class "Default")
      (node (ref "Q21") (pin "1") (pinfunction "G_1") (pintype "passive"))
      (node (ref "R24") (pin "2") (pinfunction "2_2") (pintype "passive"))
    )
    (net (code "132") (name "Net-(Q22-G)") (class "Default")
      (node (ref "Q22") (pin "1") (pinfunction "G_1") (pintype "passive"))
      (node (ref "R25") (pin "2") (pinfunction "2_2") (pintype "passive"))
    )
    (net (code "133") (name "Net-(Q23-G)") (class "Default")
      (node (ref "Q23") (pin "1") (pinfunction "G_1") (pintype "passive"))
      (node (ref "R26") (pin "2") (pinfunction "2_2") (pintype "passive"))
    )
    (net (code "134") (name "Net-(Q24-G)") (class "Default")
      (node (ref "Q24") (pin "1") (pinfunction "G_1") (pintype "passive"))
      (node (ref "R27") (pin "2") (pinfunction "2_2") (pintype "passive"))
    )
    (net (code "135") (name "Net-(Q25-G)") (class "Default")
      (node (ref "Q25") (pin "1") (pinfunction "G_1") (pintype "passive"))
      (node (ref "R28") (pin "2") (pinfunction "2_2") (pintype "passive"))
    )
    (net (code "136") (name "Net-(Q25-S)") (class "Default")
      (node (ref "J1") (pin "S1") (pinfunction "SHELL_GND_S1") (pintype "power_in"))
      (node (ref "J1") (pin "S2") (pinfunction "SHELL_GND_S2") (pintype "power_in"))
      (node (ref "J1") (pin "S3") (pinfunction "SHELL_GND_S3") (pintype "power_in"))
      (node (ref "J1") (pin "S4") (pinfunction "SHELL_GND_S4") (pintype "power_in"))
      (node (ref "Q25") (pin "2") (pinfunction "S_2") (pintype "passive"))
    )
    (net (code "137") (name "Net-(R3-Pad2)") (class "Default")
      (node (ref "R3") (pin "2") (pinfunction "2_2") (pintype "passive"))
      (node (ref "T1") (pin "B") (pinfunction "B_B") (pintype "passive"))
    )
    (net (code "138") (name "Net-(S3-O)") (class "Default")
      (node (ref "C2") (pin "1") (pinfunction "1_1") (pintype "passive"))
      (node (ref "S3") (pin "1") (pinfunction "O_1") (pintype "passive"))
    )
    (net (code "139") (name "Net-(S3-P)") (class "Default")
      (node (ref "R2") (pin "2") (pinfunction "2_2") (pintype "passive"))
      (node (ref "S3") (pin "2") (pinfunction "P_2") (pintype "passive"))
      (node (ref "U1") (pin "2") (pinfunction "TRIG_2") (pintype "input"))
      (node (ref "U1") (pin "6") (pinfunction "THRES_6") (pintype "input"))
    )
    (net (code "140") (name "Net-(S3-S)") (class "Default")
      (node (ref "C1") (pin "1") (pinfunction "1_1") (pintype "passive"))
      (node (ref "S3") (pin "3") (pinfunction "S_3") (pintype "passive"))
    )
    (net (code "141") (name "Net-(S4-P)") (class "Default")
      (node (ref "R3") (pin "1") (pinfunction "1_1") (pintype "passive"))
      (node (ref "S4") (pin "2") (pinfunction "P_2") (pintype "passive"))
    )
    (net (code "142") (name "Net-(U1-CONT)") (class "Default")
      (node (ref "C4") (pin "1") (pinfunction "1_1") (pintype "passive"))
      (node (ref "U1") (pin "5") (pinfunction "CONT_5") (pintype "bidirectional"))
    )
    (net (code "143") (name "Net-(U1-DISCH)") (class "Default")
      (node (ref "R1") (pin "2") (pinfunction "2_2") (pintype "passive"))
      (node (ref "R2") (pin "1") (pinfunction "1_1") (pintype "passive"))
      (node (ref "U1") (pin "7") (pinfunction "DISCH_7") (pintype "output"))
    )
    (net (code "144") (name "Net-(U1-VCC)") (class "Default")
      (node (ref "C3") (pin "2") (pinfunction "2_2") (pintype "passive"))
      (node (ref "R1") (pin "1") (pinfunction "1_1") (pintype "passive"))
      (node (ref "U1") (pin "8") (pinfunction "VCC_8") (pintype "power_in"))
    )
    (net (code "145") (name "Net-(VCC-P)") (class "Default")
      (node (ref "F") (pin "1") (pinfunction "1_1") (pintype "passive"))
      (node (ref "VCC") (pin "1") (pinfunction "P_1") (pintype "passive"))
    )
    (net (code "146") (name "unconnected-(IC2-~{Y9}-Pad10)") (class "Default")
      (node (ref "IC2") (pin "10") (pinfunction "~{Y9}_10") (pintype "bidirectional"))
    )
    (net (code "147") (name "unconnected-(IC2-~{Y10}-Pad11)") (class "Default")
      (node (ref "IC2") (pin "11") (pinfunction "~{Y10}_11") (pintype "bidirectional"))
    )
    (net (code "148") (name "unconnected-(IC2-~{Y11}-Pad13)") (class "Default")
      (node (ref "IC2") (pin "13") (pinfunction "~{Y11}_13") (pintype "bidirectional"))
    )
    (net (code "149") (name "unconnected-(IC2-~{Y12}-Pad14)") (class "Default")
      (node (ref "IC2") (pin "14") (pinfunction "~{Y12}_14") (pintype "bidirectional"))
    )
    (net (code "150") (name "unconnected-(IC2-~{Y13}-Pad15)") (class "Default")
      (node (ref "IC2") (pin "15") (pinfunction "~{Y13}_15") (pintype "bidirectional"))
    )
    (net (code "151") (name "unconnected-(IC2-~{Y14}-Pad16)") (class "Default")
      (node (ref "IC2") (pin "16") (pinfunction "~{Y14}_16") (pintype "bidirectional"))
    )
    (net (code "152") (name "unconnected-(IC2-~{Y15}-Pad17)") (class "Default")
      (node (ref "IC2") (pin "17") (pinfunction "~{Y15}_17") (pintype "bidirectional"))
    )
    (net (code "153") (name "unconnected-(IC3A-~{Q}-Pad2)") (class "Default")
      (node (ref "IC3") (pin "2") (pinfunction "~{Q}_2") (pintype "output"))
    )
    (net (code "154") (name "unconnected-(IC4A-~{Q}-Pad2)") (class "Default")
      (node (ref "IC4") (pin "2") (pinfunction "~{Q}_2") (pintype "output"))
    )
    (net (code "155") (name "unconnected-(IC4B-~{Q}-Pad6)") (class "Default")
      (node (ref "IC4") (pin "6") (pinfunction "~{Q}_6") (pintype "output"))
    )
    (net (code "156") (name "unconnected-(S1-P1-Pad4)") (class "Default")
      (node (ref "S1") (pin "4") (pinfunction "P1_4") (pintype "passive"))
    )
    (net (code "157") (name "unconnected-(S1-S1-Pad2)") (class "Default")
      (node (ref "S1") (pin "2") (pinfunction "S1_2") (pintype "passive"))
    )
    (net (code "158") (name "unconnected-(U3-2A-Pad9)") (class "Default")
      (node (ref "U3") (pin "9") (pinfunction "2A_9") (pintype "input"))
    )
    (net (code "159") (name "unconnected-(U3-2B-Pad10)") (class "Default")
      (node (ref "U3") (pin "10") (pinfunction "2B_10") (pintype "input"))
    )
    (net (code "160") (name "unconnected-(U3-2C-Pad12)") (class "Default")
      (node (ref "U3") (pin "12") (pinfunction "2C_12") (pintype "input"))
    )
    (net (code "161") (name "unconnected-(U3-2D-Pad13)") (class "Default")
      (node (ref "U3") (pin "13") (pinfunction "2D_13") (pintype "input"))
    )
    (net (code "162") (name "unconnected-(U3-2Y-Pad8)") (class "Default")
      (node (ref "U3") (pin "8") (pinfunction "2Y_8") (pintype "output"))
    )
    (net (code "163") (name "unconnected-(U3-N.C.-Pad11)") (class "Default")
      (node (ref "U3") (pin "11") (pinfunction "N.C._11") (pintype "no_connect"))
    )
    (net (code "164") (name "unconnected-(U3-N.C._2-Pad3)") (class "Default")
      (node (ref "U3") (pin "3") (pinfunction "N.C._2_3") (pintype "no_connect"))
    )
    (net (code "165") (name "unconnected-(U4-NC-Pad1)") (class "Default")
      (node (ref "U4") (pin "1") (pinfunction "NC_1") (pintype "passive"))
    )
  )
)
